# r3eflow-v3.net
KiCad netlist of a schematic drawn in EAGLE
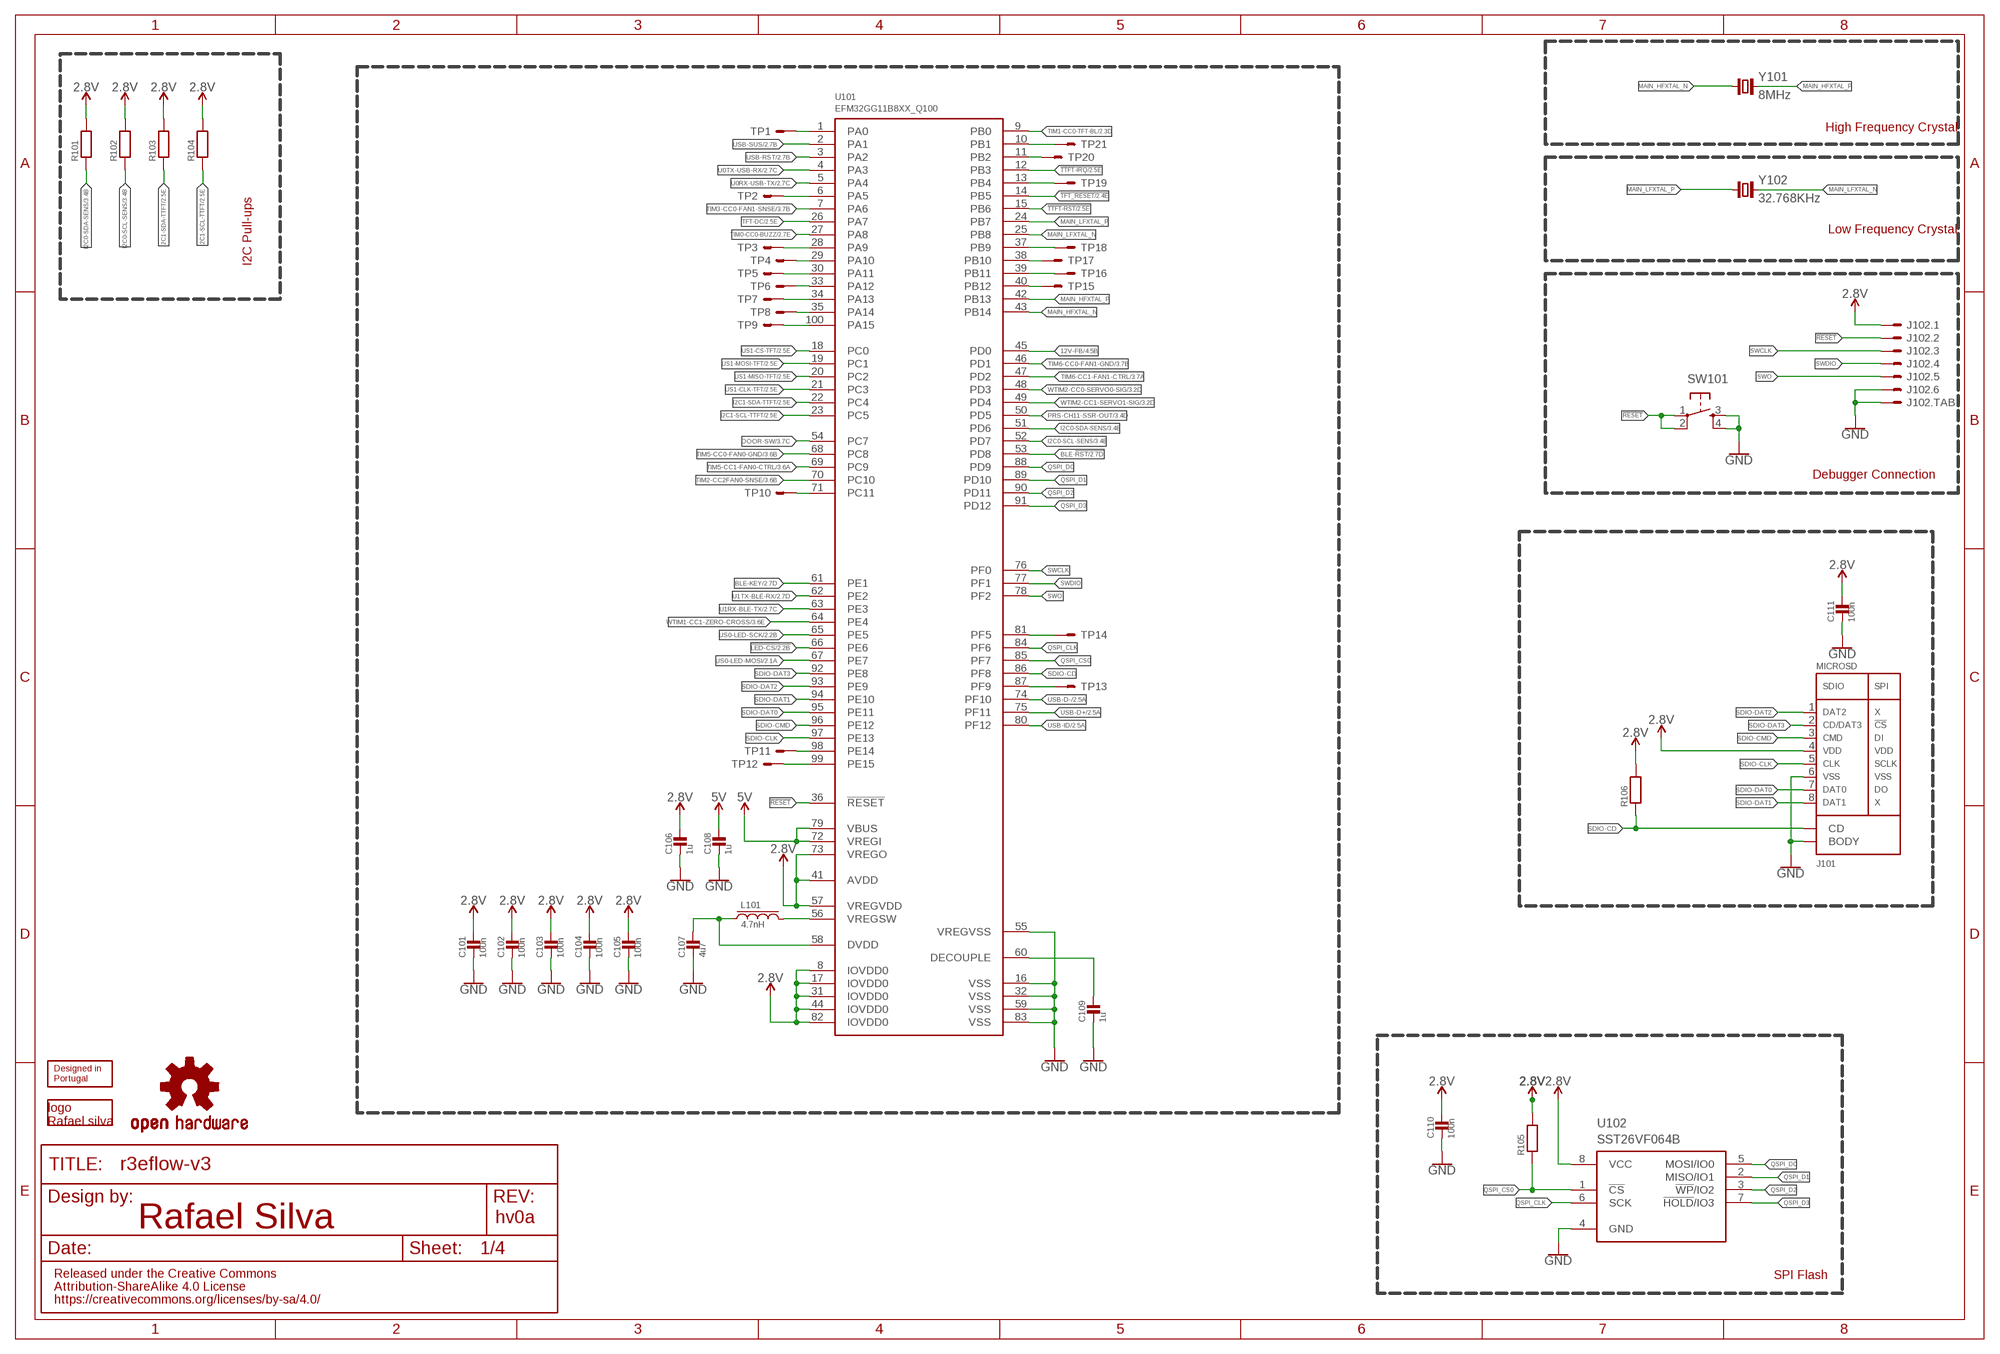
[diagram p0: schematic, sheet 1]
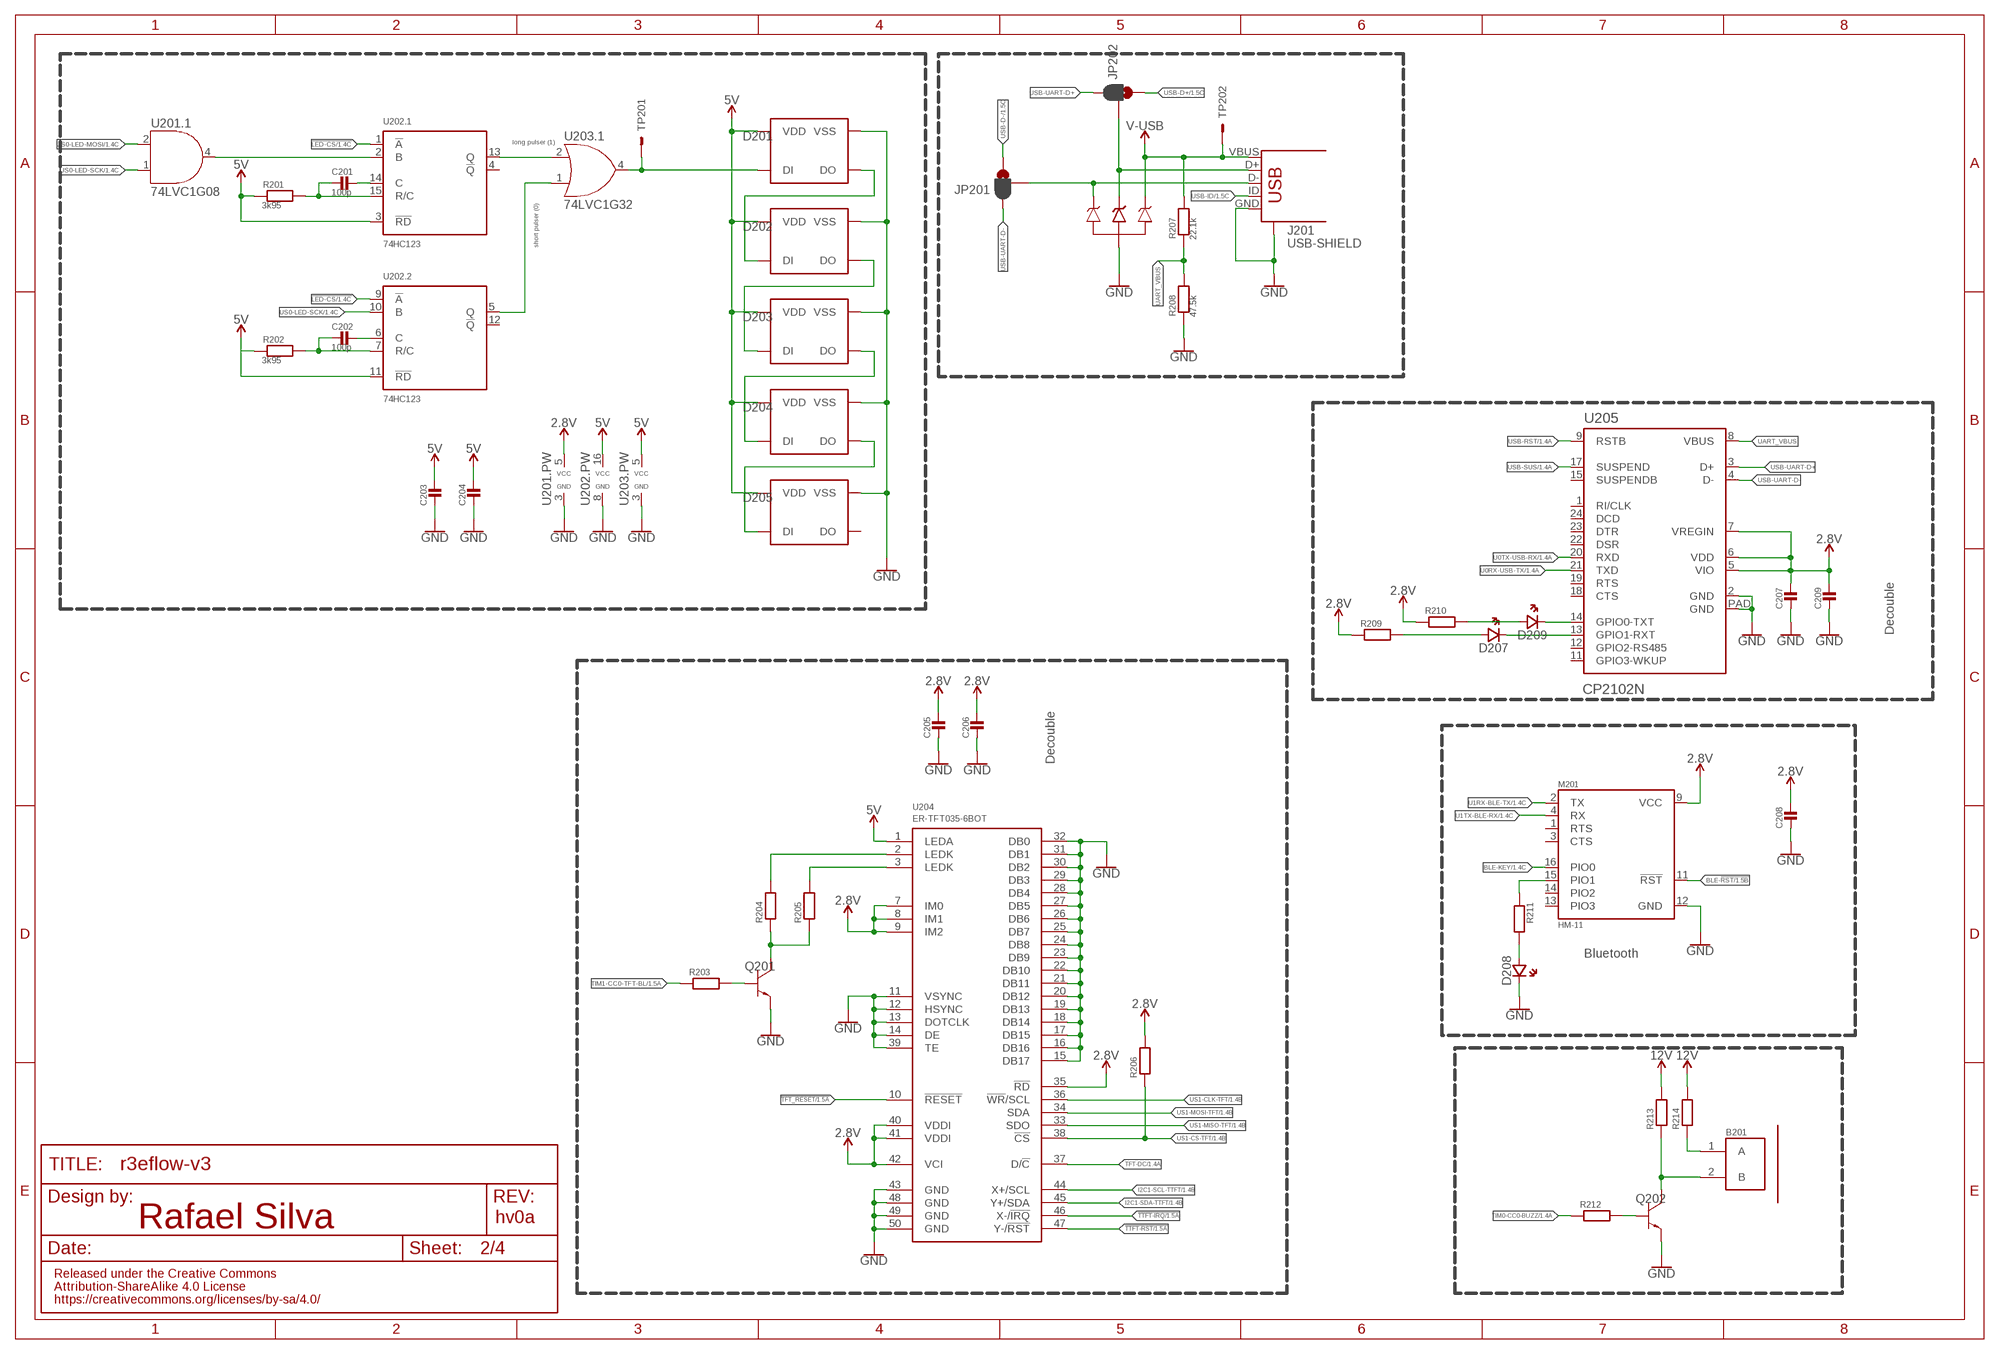
[diagram p1: schematic, sheet 2]
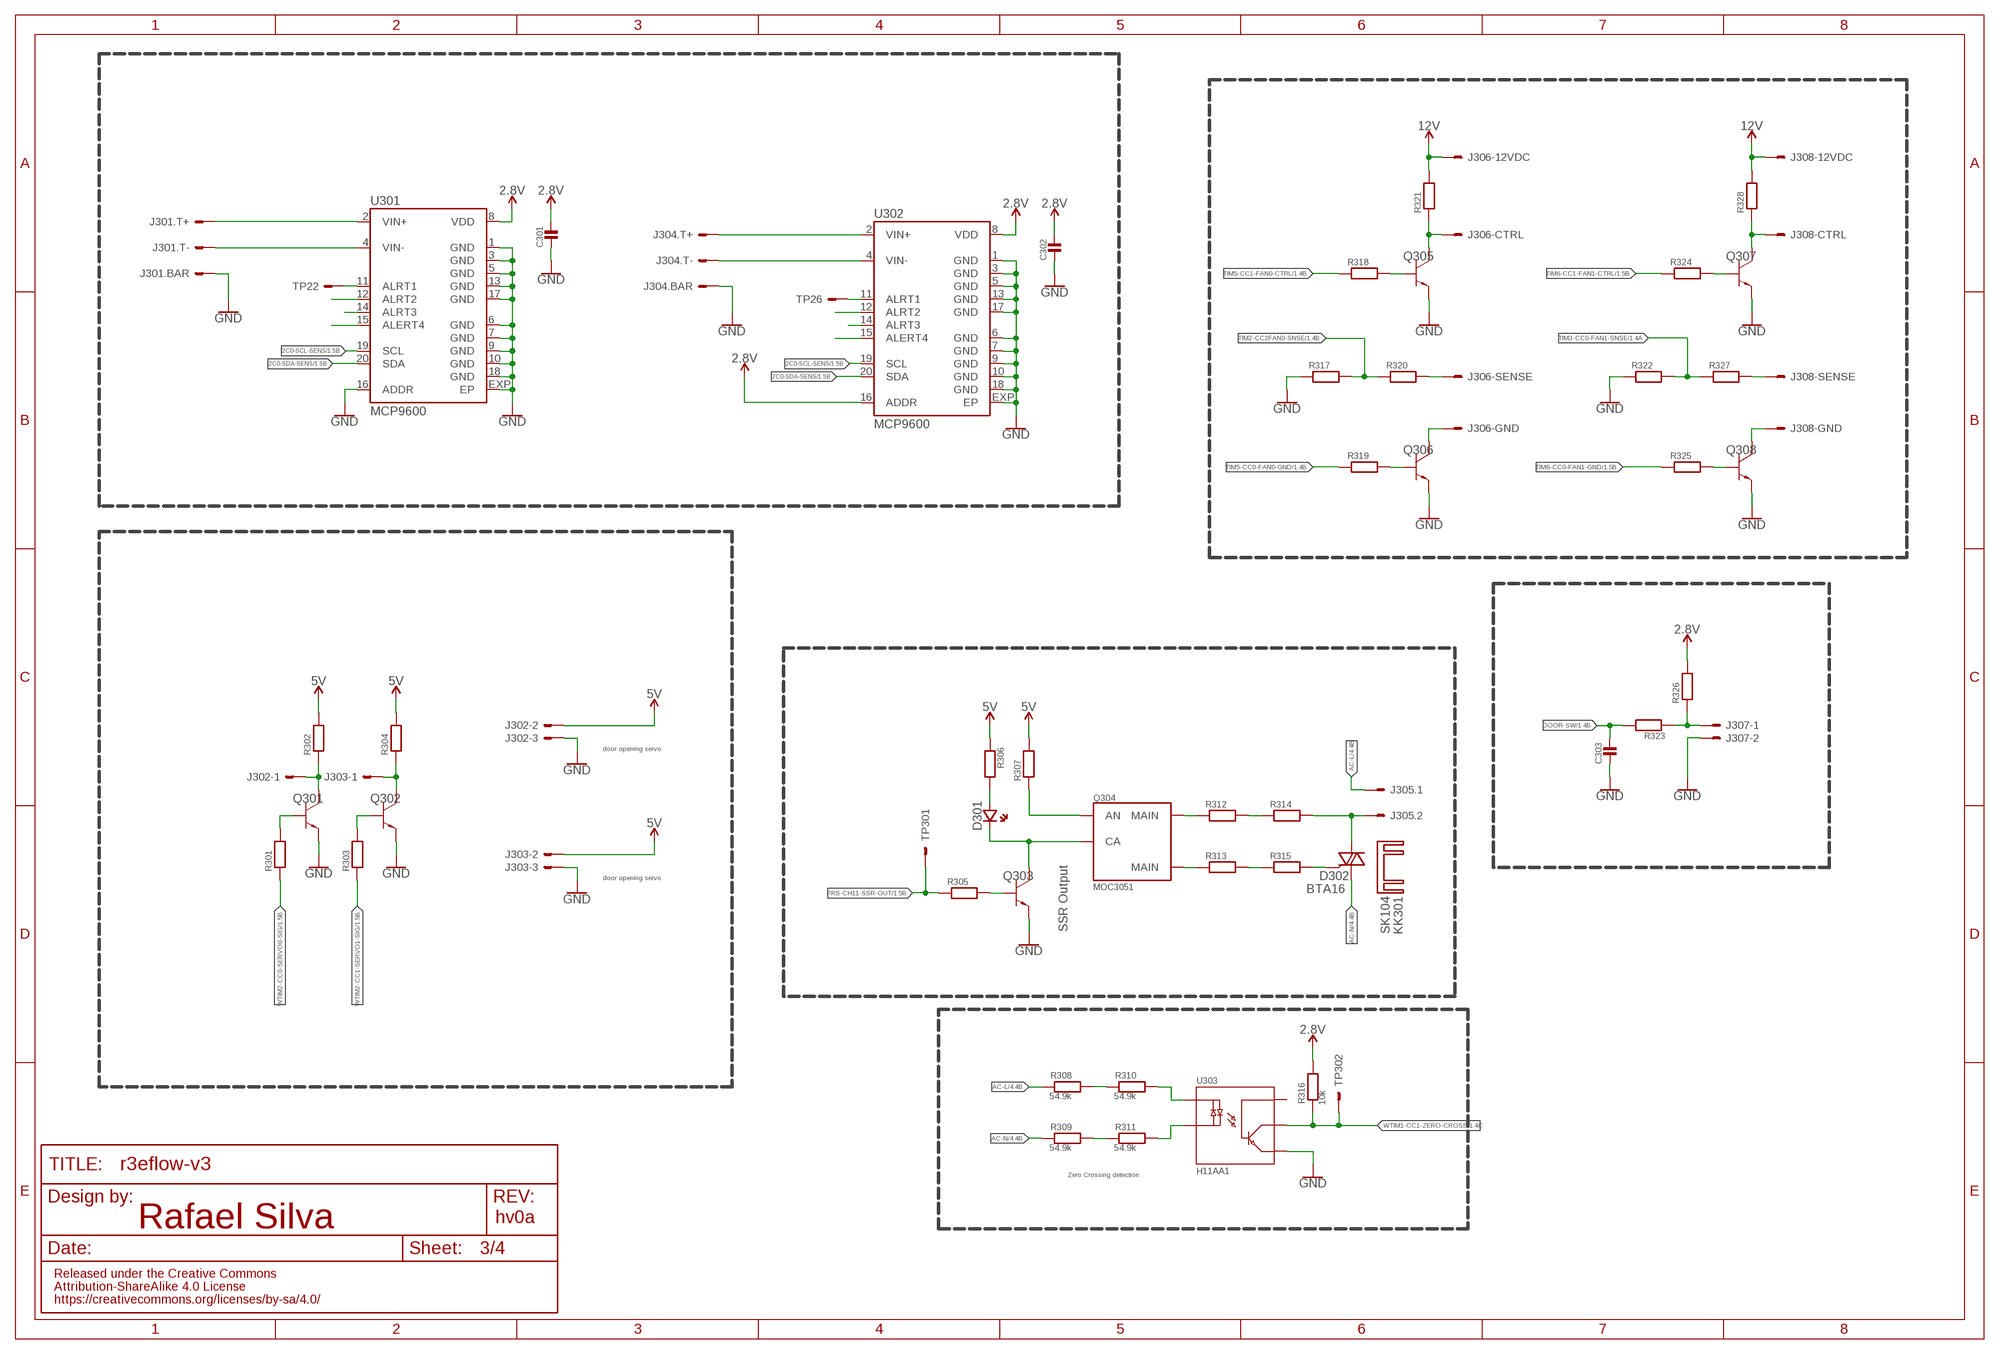
[diagram p2: schematic, sheet 3]
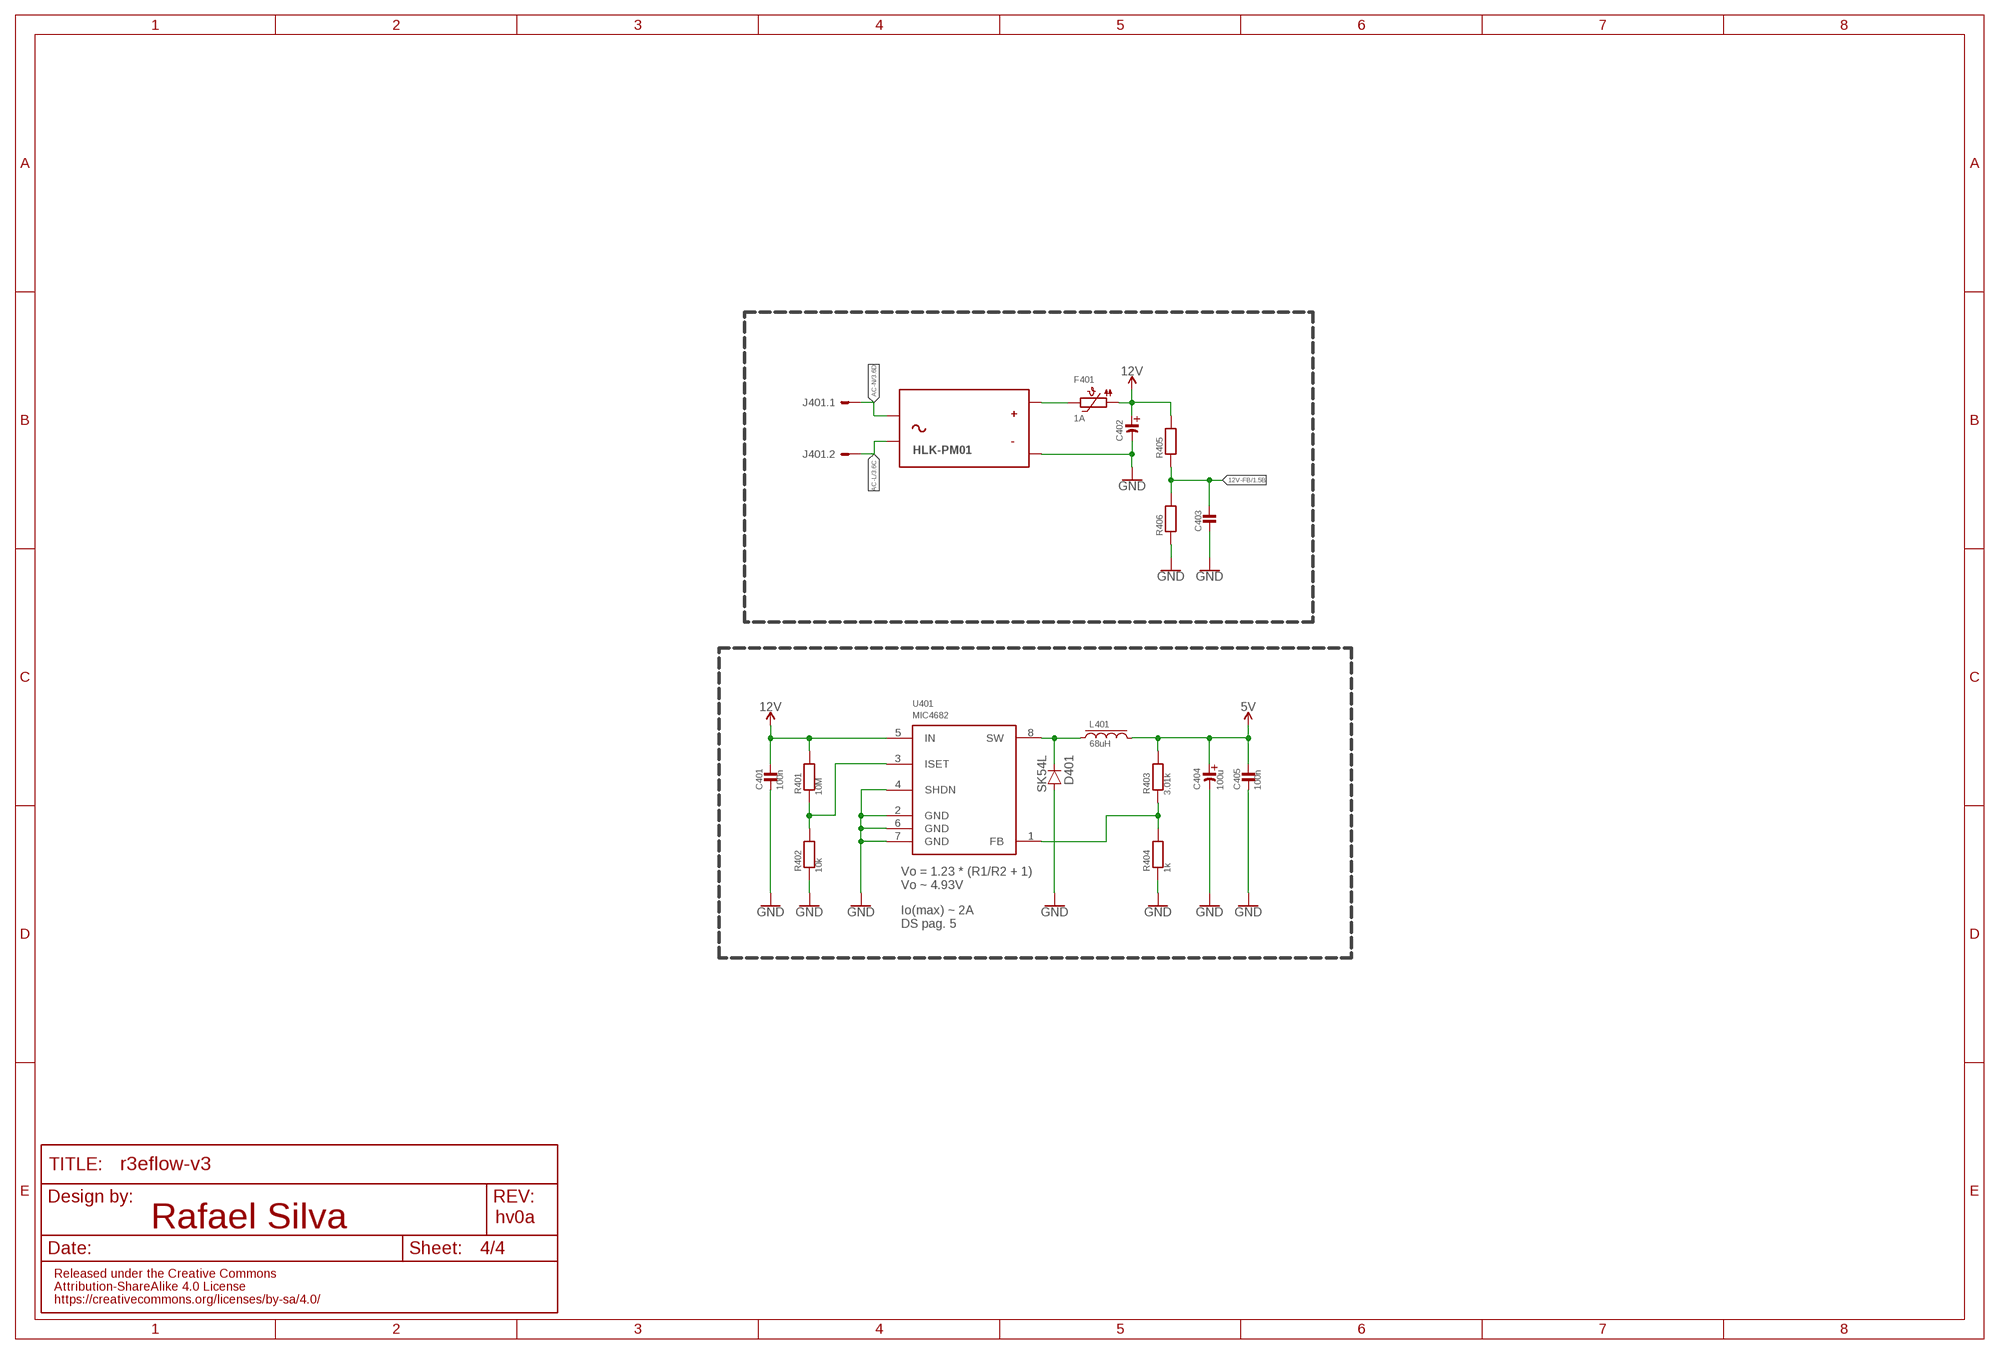
[diagram p3: schematic, sheet 4]

(export (version "E")
  (design (tool "Eeschema 10.0.6"))
  (components
    (comp (ref "B201")
      (value "PKLCS1212E2400-R1")
      (footprint "eagle-import:BUZZ_PIEZO_SMD")
      (libsource (lib "eagle-import") (part "PKLCS1212E2400-R1"))
    )
    (comp (ref "C201")
      (value "100p")
      (footprint "eagle-import:0603_WAVE")
      (libsource (lib "eagle-import") (part "MLCC0603"))
    )
    (comp (ref "C202")
      (value "100p")
      (footprint "eagle-import:0603_WAVE")
      (libsource (lib "eagle-import") (part "MLCC0603"))
    )
    (comp (ref "C203")
      (value "MLCC0603")
      (footprint "eagle-import:0603_WAVE")
      (libsource (lib "eagle-import") (part "MLCC0603"))
    )
    (comp (ref "C204")
      (value "MLCC0603")
      (footprint "eagle-import:0603_WAVE")
      (libsource (lib "eagle-import") (part "MLCC0603"))
    )
    (comp (ref "C205")
      (value "MLCC0603")
      (footprint "eagle-import:0603_WAVE")
      (libsource (lib "eagle-import") (part "MLCC0603"))
    )
    (comp (ref "C206")
      (value "MLCC0603")
      (footprint "eagle-import:0603_WAVE")
      (libsource (lib "eagle-import") (part "MLCC0603"))
    )
    (comp (ref "C207")
      (value "MLCC0603")
      (footprint "eagle-import:0603_WAVE")
      (libsource (lib "eagle-import") (part "MLCC0603"))
    )
    (comp (ref "C208")
      (value "MLCC0603")
      (footprint "eagle-import:0603_WAVE")
      (libsource (lib "eagle-import") (part "MLCC0603"))
    )
    (comp (ref "C209")
      (value "MLCC0603")
      (footprint "eagle-import:0603_WAVE")
      (libsource (lib "eagle-import") (part "MLCC0603"))
    )
    (comp (ref "D201")
      (value "WS2812B")
      (footprint "eagle-import:3535")
      (libsource (lib "eagle-import") (part "WS2812B3535"))
    )
    (comp (ref "D202")
      (value "WS2812B")
      (footprint "eagle-import:3535")
      (libsource (lib "eagle-import") (part "WS2812B3535"))
    )
    (comp (ref "D203")
      (value "WS2812B")
      (footprint "eagle-import:3535")
      (libsource (lib "eagle-import") (part "WS2812B3535"))
    )
    (comp (ref "D204")
      (value "WS2812B")
      (footprint "eagle-import:3535")
      (libsource (lib "eagle-import") (part "WS2812B3535"))
    )
    (comp (ref "D205")
      (value "WS2812B")
      (footprint "eagle-import:3535")
      (libsource (lib "eagle-import") (part "WS2812B3535"))
    )
    (comp (ref "D206")
      (value "SP0503BAHT")
      (footprint "eagle-import:SOT143")
      (libsource (lib "eagle-import") (part "SP0503BAHT"))
    )
    (comp (ref "D207")
      (value "LED0603")
      (footprint "eagle-import:CHIPLED_0603")
      (libsource (lib "eagle-import") (part "LED0603"))
    )
    (comp (ref "D208")
      (value "LED0603")
      (footprint "eagle-import:CHIPLED_0603")
      (libsource (lib "eagle-import") (part "LED0603"))
    )
    (comp (ref "D209")
      (value "LED0603")
      (footprint "eagle-import:CHIPLED_0603")
      (libsource (lib "eagle-import") (part "LED0603"))
    )
    (comp (ref "J201")
      (value "USB-SHIELD")
      (footprint "eagle-import:USB-M-S1")
      (libsource (lib "eagle-import") (part "USB-SHIELD"))
    )
    (comp (ref "JP201")
      (value "JUMPER-SMT_3_1-NC_PASTE_SILK")
      (footprint "eagle-import:SMT-JUMPER_3_1-NC_PASTE_SILK")
      (libsource (lib "eagle-import") (part "JUMPER-SMT_3_1-NC_PASTE_SILK"))
    )
    (comp (ref "JP202")
      (value "JUMPER-SMT_3_1-NC_PASTE_SILK")
      (footprint "eagle-import:SMT-JUMPER_3_1-NC_PASTE_SILK")
      (libsource (lib "eagle-import") (part "JUMPER-SMT_3_1-NC_PASTE_SILK"))
    )
    (comp (ref "M201")
      (value "HM-11")
      (footprint "eagle-import:HM-11")
      (libsource (lib "eagle-import") (part "HM-11"))
    )
    (comp (ref "Q201")
      (value "BC817-40")
      (footprint "eagle-import:SOT-23-3")
      (libsource (lib "eagle-import") (part "BC817-40"))
    )
    (comp (ref "Q202")
      (value "BC817-40")
      (footprint "eagle-import:SOT-23-3")
      (libsource (lib "eagle-import") (part "BC817-40"))
    )
    (comp (ref "R201")
      (value "3k95")
      (footprint "eagle-import:0603_WAVE")
      (libsource (lib "eagle-import") (part "RESISTOR0603"))
    )
    (comp (ref "R202")
      (value "3k95")
      (footprint "eagle-import:0603_WAVE")
      (libsource (lib "eagle-import") (part "RESISTOR0603"))
    )
    (comp (ref "R203")
      (value "RESISTOR0603")
      (footprint "eagle-import:0603_WAVE")
      (libsource (lib "eagle-import") (part "RESISTOR0603"))
    )
    (comp (ref "R204")
      (value "RESISTOR0603")
      (footprint "eagle-import:0603_WAVE")
      (libsource (lib "eagle-import") (part "RESISTOR0603"))
    )
    (comp (ref "R205")
      (value "RESISTOR0603")
      (footprint "eagle-import:0603_WAVE")
      (libsource (lib "eagle-import") (part "RESISTOR0603"))
    )
    (comp (ref "R206")
      (value "RESISTOR0603")
      (footprint "eagle-import:0603_WAVE")
      (libsource (lib "eagle-import") (part "RESISTOR0603"))
    )
    (comp (ref "R207")
      (value "22.1k")
      (footprint "eagle-import:0603_WAVE")
      (libsource (lib "eagle-import") (part "RESISTOR0603"))
    )
    (comp (ref "R208")
      (value "47.5k")
      (footprint "eagle-import:0603_WAVE")
      (libsource (lib "eagle-import") (part "RESISTOR0603"))
    )
    (comp (ref "R209")
      (value "RESISTOR0603")
      (footprint "eagle-import:0603_WAVE")
      (libsource (lib "eagle-import") (part "RESISTOR0603"))
    )
    (comp (ref "R210")
      (value "RESISTOR0603")
      (footprint "eagle-import:0603_WAVE")
      (libsource (lib "eagle-import") (part "RESISTOR0603"))
    )
    (comp (ref "R211")
      (value "RESISTOR0603")
      (footprint "eagle-import:0603_WAVE")
      (libsource (lib "eagle-import") (part "RESISTOR0603"))
    )
    (comp (ref "R212")
      (value "RESISTOR0603")
      (footprint "eagle-import:0603_WAVE")
      (libsource (lib "eagle-import") (part "RESISTOR0603"))
    )
    (comp (ref "R213")
      (value "RESISTOR0603")
      (footprint "eagle-import:0603_WAVE")
      (libsource (lib "eagle-import") (part "RESISTOR0603"))
    )
    (comp (ref "R214")
      (value "RESISTOR0603")
      (footprint "eagle-import:0603_WAVE")
      (libsource (lib "eagle-import") (part "RESISTOR0603"))
    )
    (comp (ref "TP201")
      (value "TEST_POINT")
      (footprint "eagle-import:TEST_POINT")
      (libsource (lib "eagle-import") (part "TEST_POINT"))
    )
    (comp (ref "TP202")
      (value "TEST_POINT")
      (footprint "eagle-import:TEST_POINT")
      (libsource (lib "eagle-import") (part "TEST_POINT"))
    )
    (comp (ref "U201")
      (value "74LVC1G08")
      (footprint "eagle-import:SC-70-5")
      (libsource (lib "eagle-import") (part "74LVC1G08"))
    )
    (comp (ref "U202")
      (value "74HC123")
      (footprint "eagle-import:TSSOP-16")
      (libsource (lib "eagle-import") (part "74HC123"))
    )
    (comp (ref "U203")
      (value "74LVC1G32")
      (footprint "eagle-import:SC-70-5")
      (libsource (lib "eagle-import") (part "74LVC1G32"))
    )
    (comp (ref "U204")
      (value "ER-TFT035-6BOT")
      (footprint "eagle-import:ZIF50-TFT_BACK")
      (libsource (lib "eagle-import") (part "ER-TFT035-6BOT"))
    )
    (comp (ref "U205")
      (value "CP2102N")
      (footprint "eagle-import:QFN24")
      (libsource (lib "eagle-import") (part "CP2102N"))
    )
    (comp (ref "C301")
      (value "MLCC0603")
      (footprint "eagle-import:0603_WAVE")
      (libsource (lib "eagle-import") (part "MLCC0603"))
    )
    (comp (ref "C302")
      (value "MLCC0603")
      (footprint "eagle-import:0603_WAVE")
      (libsource (lib "eagle-import") (part "MLCC0603"))
    )
    (comp (ref "C303")
      (value "MLCC0603")
      (footprint "eagle-import:0603_WAVE")
      (libsource (lib "eagle-import") (part "MLCC0603"))
    )
    (comp (ref "D301")
      (value "LED0603")
      (footprint "eagle-import:CHIPLED_0603")
      (libsource (lib "eagle-import") (part "LED0603"))
    )
    (comp (ref "D302")
      (value "BTA16")
      (footprint "eagle-import:TO220DS")
      (libsource (lib "eagle-import") (part "BTA16"))
    )
    (comp (ref "J301")
      (value "PCC-SMP")
      (footprint "eagle-import:PCC-SMP")
      (libsource (lib "eagle-import") (part "PCC-SMP"))
    )
    (comp (ref "J302")
      (value "3X1_2.54")
      (footprint "eagle-import:3X1_2.54")
      (libsource (lib "eagle-import") (part "3X1_2.54"))
    )
    (comp (ref "J303")
      (value "3X1_2.54")
      (footprint "eagle-import:3X1_2.54")
      (libsource (lib "eagle-import") (part "3X1_2.54"))
    )
    (comp (ref "J304")
      (value "PCC-SMP")
      (footprint "eagle-import:PCC-SMP")
      (libsource (lib "eagle-import") (part "PCC-SMP"))
    )
    (comp (ref "J305")
      (value "2EDG-2P")
      (footprint "eagle-import:2EDG-2P")
      (libsource (lib "eagle-import") (part "2EDG-2P"))
    )
    (comp (ref "J306")
      (value "4P-PC-FAN")
      (footprint "eagle-import:KF2510-3+1P")
      (libsource (lib "eagle-import") (part "4P-PC-FAN"))
    )
    (comp (ref "J307")
      (value "2X1_2.54")
      (footprint "eagle-import:2X1_2.54")
      (libsource (lib "eagle-import") (part "2X1_2.54"))
    )
    (comp (ref "J308")
      (value "4P-PC-FAN")
      (footprint "eagle-import:KF2510-3+1P")
      (libsource (lib "eagle-import") (part "4P-PC-FAN"))
    )
    (comp (ref "KK301")
      (value "SK104")
      (footprint "eagle-import:SK104")
      (libsource (lib "eagle-import") (part "SK104"))
    )
    (comp (ref "Q301")
      (value "BC817-40")
      (footprint "eagle-import:SOT-23-3")
      (libsource (lib "eagle-import") (part "BC817-40"))
    )
    (comp (ref "Q302")
      (value "BC817-40")
      (footprint "eagle-import:SOT-23-3")
      (libsource (lib "eagle-import") (part "BC817-40"))
    )
    (comp (ref "Q303")
      (value "BC817-40")
      (footprint "eagle-import:SOT-23-3")
      (libsource (lib "eagle-import") (part "BC817-40"))
    )
    (comp (ref "Q304")
      (value "MOC3051")
      (footprint "eagle-import:DIP-6-SMD")
      (libsource (lib "eagle-import") (part "MOC3051"))
    )
    (comp (ref "Q305")
      (value "BC817-40")
      (footprint "eagle-import:SOT-23-3")
      (libsource (lib "eagle-import") (part "BC817-40"))
    )
    (comp (ref "Q306")
      (value "BC817-40")
      (footprint "eagle-import:SOT-23-3")
      (libsource (lib "eagle-import") (part "BC817-40"))
    )
    (comp (ref "Q307")
      (value "BC817-40")
      (footprint "eagle-import:SOT-23-3")
      (libsource (lib "eagle-import") (part "BC817-40"))
    )
    (comp (ref "Q308")
      (value "BC817-40")
      (footprint "eagle-import:SOT-23-3")
      (libsource (lib "eagle-import") (part "BC817-40"))
    )
    (comp (ref "R301")
      (value "RESISTOR0603")
      (footprint "eagle-import:0603_WAVE")
      (libsource (lib "eagle-import") (part "RESISTOR0603"))
    )
    (comp (ref "R302")
      (value "RESISTOR0603")
      (footprint "eagle-import:0603_WAVE")
      (libsource (lib "eagle-import") (part "RESISTOR0603"))
    )
    (comp (ref "R303")
      (value "RESISTOR0603")
      (footprint "eagle-import:0603_WAVE")
      (libsource (lib "eagle-import") (part "RESISTOR0603"))
    )
    (comp (ref "R304")
      (value "RESISTOR0603")
      (footprint "eagle-import:0603_WAVE")
      (libsource (lib "eagle-import") (part "RESISTOR0603"))
    )
    (comp (ref "R305")
      (value "RESISTOR0603")
      (footprint "eagle-import:0603_WAVE")
      (libsource (lib "eagle-import") (part "RESISTOR0603"))
    )
    (comp (ref "R306")
      (value "RESISTOR0603")
      (footprint "eagle-import:0603_WAVE")
      (libsource (lib "eagle-import") (part "RESISTOR0603"))
    )
    (comp (ref "R307")
      (value "RESISTOR0603")
      (footprint "eagle-import:0603_WAVE")
      (libsource (lib "eagle-import") (part "RESISTOR0603"))
    )
    (comp (ref "R308")
      (value "54.9k")
      (footprint "eagle-import:_1206")
      (libsource (lib "eagle-import") (part "RESISTOR_1206"))
    )
    (comp (ref "R309")
      (value "54.9k")
      (footprint "eagle-import:_1206")
      (libsource (lib "eagle-import") (part "RESISTOR_1206"))
    )
    (comp (ref "R310")
      (value "54.9k")
      (footprint "eagle-import:_1206")
      (libsource (lib "eagle-import") (part "RESISTOR_1206"))
    )
    (comp (ref "R311")
      (value "54.9k")
      (footprint "eagle-import:_1206")
      (libsource (lib "eagle-import") (part "RESISTOR_1206"))
    )
    (comp (ref "R312")
      (value "RESISTOR_1206")
      (footprint "eagle-import:_1206")
      (libsource (lib "eagle-import") (part "RESISTOR_1206"))
    )
    (comp (ref "R313")
      (value "RESISTOR_1206")
      (footprint "eagle-import:_1206")
      (libsource (lib "eagle-import") (part "RESISTOR_1206"))
    )
    (comp (ref "R314")
      (value "RESISTOR_1206")
      (footprint "eagle-import:_1206")
      (libsource (lib "eagle-import") (part "RESISTOR_1206"))
    )
    (comp (ref "R315")
      (value "RESISTOR_1206")
      (footprint "eagle-import:_1206")
      (libsource (lib "eagle-import") (part "RESISTOR_1206"))
    )
    (comp (ref "R316")
      (value "10k")
      (footprint "eagle-import:0603_WAVE")
      (libsource (lib "eagle-import") (part "RESISTOR0603"))
    )
    (comp (ref "R317")
      (value "RESISTOR0603")
      (footprint "eagle-import:0603_WAVE")
      (libsource (lib "eagle-import") (part "RESISTOR0603"))
    )
    (comp (ref "R318")
      (value "RESISTOR0603")
      (footprint "eagle-import:0603_WAVE")
      (libsource (lib "eagle-import") (part "RESISTOR0603"))
    )
    (comp (ref "R319")
      (value "RESISTOR0603")
      (footprint "eagle-import:0603_WAVE")
      (libsource (lib "eagle-import") (part "RESISTOR0603"))
    )
    (comp (ref "R320")
      (value "RESISTOR0603")
      (footprint "eagle-import:0603_WAVE")
      (libsource (lib "eagle-import") (part "RESISTOR0603"))
    )
    (comp (ref "R321")
      (value "RESISTOR0603")
      (footprint "eagle-import:0603_WAVE")
      (libsource (lib "eagle-import") (part "RESISTOR0603"))
    )
    (comp (ref "R322")
      (value "RESISTOR0603")
      (footprint "eagle-import:0603_WAVE")
      (libsource (lib "eagle-import") (part "RESISTOR0603"))
    )
    (comp (ref "R323")
      (value "RESISTOR0603")
      (footprint "eagle-import:0603_WAVE")
      (libsource (lib "eagle-import") (part "RESISTOR0603"))
    )
    (comp (ref "R324")
      (value "RESISTOR0603")
      (footprint "eagle-import:0603_WAVE")
      (libsource (lib "eagle-import") (part "RESISTOR0603"))
    )
    (comp (ref "R325")
      (value "RESISTOR0603")
      (footprint "eagle-import:0603_WAVE")
      (libsource (lib "eagle-import") (part "RESISTOR0603"))
    )
    (comp (ref "R326")
      (value "RESISTOR0603")
      (footprint "eagle-import:0603_WAVE")
      (libsource (lib "eagle-import") (part "RESISTOR0603"))
    )
    (comp (ref "R327")
      (value "RESISTOR0603")
      (footprint "eagle-import:0603_WAVE")
      (libsource (lib "eagle-import") (part "RESISTOR0603"))
    )
    (comp (ref "R328")
      (value "RESISTOR0603")
      (footprint "eagle-import:0603_WAVE")
      (libsource (lib "eagle-import") (part "RESISTOR0603"))
    )
    (comp (ref "TP22")
      (value "TEST_POINT")
      (footprint "eagle-import:TEST_POINT")
      (libsource (lib "eagle-import") (part "TEST_POINT"))
    )
    (comp (ref "TP26")
      (value "TEST_POINT")
      (footprint "eagle-import:TEST_POINT")
      (libsource (lib "eagle-import") (part "TEST_POINT"))
    )
    (comp (ref "TP301")
      (value "TEST_POINT")
      (footprint "eagle-import:TEST_POINT")
      (libsource (lib "eagle-import") (part "TEST_POINT"))
    )
    (comp (ref "TP302")
      (value "TEST_POINT")
      (footprint "eagle-import:TEST_POINT")
      (libsource (lib "eagle-import") (part "TEST_POINT"))
    )
    (comp (ref "U301")
      (value "MCP9600")
      (footprint "eagle-import:TQFN20-5X5")
      (libsource (lib "eagle-import") (part "MCP9600"))
    )
    (comp (ref "U302")
      (value "MCP9600")
      (footprint "eagle-import:TQFN20-5X5")
      (libsource (lib "eagle-import") (part "MCP9600"))
    )
    (comp (ref "U303")
      (value "H11AA1")
      (footprint "eagle-import:DIP-6-SMD")
      (libsource (lib "eagle-import") (part "H11AA1"))
    )
    (comp (ref "ACDC401")
      (value "HLK-PM01")
      (footprint "eagle-import:HLK-PM01")
      (libsource (lib "eagle-import") (part "HLK-PM01"))
    )
    (comp (ref "C401")
      (value "100n")
      (footprint "eagle-import:0603_WAVE")
      (libsource (lib "eagle-import") (part "MLCC0603"))
    )
    (comp (ref "C402")
      (value "CAPACITOR_ELD")
      (footprint "eagle-import:PANASONIC_D")
      (libsource (lib "eagle-import") (part "CAPACITOR_ELD"))
    )
    (comp (ref "C403")
      (value "MLCC0603")
      (footprint "eagle-import:0603_WAVE")
      (libsource (lib "eagle-import") (part "MLCC0603"))
    )
    (comp (ref "C404")
      (value "100u")
      (footprint "eagle-import:PANASONIC_D")
      (libsource (lib "eagle-import") (part "CAPACITOR_ELD"))
    )
    (comp (ref "C405")
      (value "100n")
      (footprint "eagle-import:0603_WAVE")
      (libsource (lib "eagle-import") (part "MLCC0603"))
    )
    (comp (ref "D401")
      (value "SK54L")
      (footprint "eagle-import:DO214AA")
      (libsource (lib "eagle-import") (part "SK54L"))
    )
    (comp (ref "F401")
      (value "1A")
      (footprint "eagle-import:PTC1812")
      (libsource (lib "eagle-import") (part "PTC1812"))
    )
    (comp (ref "J401")
      (value "2EDG-2P")
      (footprint "eagle-import:2EDG-2P")
      (libsource (lib "eagle-import") (part "2EDG-2P"))
    )
    (comp (ref "L401")
      (value "68uH")
      (footprint "eagle-import:1207")
      (libsource (lib "eagle-import") (part "INDUCTOR1207"))
    )
    (comp (ref "R401")
      (value "10M")
      (footprint "eagle-import:0603_WAVE")
      (libsource (lib "eagle-import") (part "RESISTOR0603"))
    )
    (comp (ref "R402")
      (value "10k")
      (footprint "eagle-import:0603_WAVE")
      (libsource (lib "eagle-import") (part "RESISTOR0603"))
    )
    (comp (ref "R403")
      (value "3.01k")
      (footprint "eagle-import:0603_WAVE")
      (libsource (lib "eagle-import") (part "RESISTOR0603"))
    )
    (comp (ref "R404")
      (value "1k")
      (footprint "eagle-import:0603_WAVE")
      (libsource (lib "eagle-import") (part "RESISTOR0603"))
    )
    (comp (ref "R405")
      (value "RESISTOR0603")
      (footprint "eagle-import:0603_WAVE")
      (libsource (lib "eagle-import") (part "RESISTOR0603"))
    )
    (comp (ref "R406")
      (value "RESISTOR0603")
      (footprint "eagle-import:0603_WAVE")
      (libsource (lib "eagle-import") (part "RESISTOR0603"))
    )
    (comp (ref "U401")
      (value "MIC4682")
      (footprint "eagle-import:SOIC8")
      (libsource (lib "eagle-import") (part "MIC4682"))
    )
    (comp (ref "C101")
      (value "100n")
      (footprint "eagle-import:0603_WAVE")
      (libsource (lib "eagle-import") (part "MLCC0603"))
    )
    (comp (ref "C102")
      (value "100n")
      (footprint "eagle-import:0603_WAVE")
      (libsource (lib "eagle-import") (part "MLCC0603"))
    )
    (comp (ref "C103")
      (value "100n")
      (footprint "eagle-import:0603_WAVE")
      (libsource (lib "eagle-import") (part "MLCC0603"))
    )
    (comp (ref "C104")
      (value "100n")
      (footprint "eagle-import:0603_WAVE")
      (libsource (lib "eagle-import") (part "MLCC0603"))
    )
    (comp (ref "C105")
      (value "100n")
      (footprint "eagle-import:0603_WAVE")
      (libsource (lib "eagle-import") (part "MLCC0603"))
    )
    (comp (ref "C106")
      (value "1u")
      (footprint "eagle-import:0603_WAVE")
      (libsource (lib "eagle-import") (part "MLCC0603"))
    )
    (comp (ref "C107")
      (value "4u7")
      (footprint "eagle-import:0603_WAVE")
      (libsource (lib "eagle-import") (part "MLCC0603"))
    )
    (comp (ref "C108")
      (value "1u")
      (footprint "eagle-import:0603_WAVE")
      (libsource (lib "eagle-import") (part "MLCC0603"))
    )
    (comp (ref "C109")
      (value "1u")
      (footprint "eagle-import:0603_WAVE")
      (libsource (lib "eagle-import") (part "MLCC0603"))
    )
    (comp (ref "C110")
      (value "100n")
      (footprint "eagle-import:0603_WAVE")
      (libsource (lib "eagle-import") (part "MLCC0603"))
    )
    (comp (ref "C111")
      (value "100n")
      (footprint "eagle-import:0603_WAVE")
      (libsource (lib "eagle-import") (part "MLCC0603"))
    )
    (comp (ref "J101")
      (value "MICROSD")
      (footprint "eagle-import:MICRO-SD")
      (libsource (lib "eagle-import") (part "MICROSD"))
    )
    (comp (ref "J102")
      (value "SH-6")
      (footprint "eagle-import:SM06B-SSR-H-TB")
      (libsource (lib "eagle-import") (part "SH-6"))
    )
    (comp (ref "L101")
      (value "4.7nH")
      (footprint "eagle-import:_0805")
      (libsource (lib "eagle-import") (part "INDUCTOR"))
    )
    (comp (ref "LOGO101")
      (value "DESIGNEDINPT")
      (footprint "eagle-import:DESIGNEDINPT")
      (libsource (lib "eagle-import") (part "DESIGNEDINPT"))
    )
    (comp (ref "LOGO102")
      (value "RAFAEL_SILVA")
      (footprint "eagle-import:RAFAEL_SILVA_5MM_ALT_3")
      (libsource (lib "eagle-import") (part "RAFAEL_SILVA"))
    )
    (comp (ref "LOGO103")
      (value "OSHW-LOGOL")
      (footprint "eagle-import:OSHW-LOGO-L")
      (libsource (lib "eagle-import") (part "OSHW-LOGOL"))
    )
    (comp (ref "R101")
      (value "RESISTOR0603")
      (footprint "eagle-import:0603_WAVE")
      (libsource (lib "eagle-import") (part "RESISTOR0603"))
    )
    (comp (ref "R102")
      (value "RESISTOR0603")
      (footprint "eagle-import:0603_WAVE")
      (libsource (lib "eagle-import") (part "RESISTOR0603"))
    )
    (comp (ref "R103")
      (value "RESISTOR0603")
      (footprint "eagle-import:0603_WAVE")
      (libsource (lib "eagle-import") (part "RESISTOR0603"))
    )
    (comp (ref "R104")
      (value "RESISTOR0603")
      (footprint "eagle-import:0603_WAVE")
      (libsource (lib "eagle-import") (part "RESISTOR0603"))
    )
    (comp (ref "R105")
      (value "RESISTOR0603")
      (footprint "eagle-import:0603_WAVE")
      (libsource (lib "eagle-import") (part "RESISTOR0603"))
    )
    (comp (ref "R106")
      (value "RESISTOR0603")
      (footprint "eagle-import:0603_WAVE")
      (libsource (lib "eagle-import") (part "RESISTOR0603"))
    )
    (comp (ref "SW101")
      (value "PUSH_BUTTON")
      (footprint "eagle-import:PUSH_BUTTON")
      (libsource (lib "eagle-import") (part "PUSH_BUTTON"))
    )
    (comp (ref "TP1")
      (value "TEST_POINT")
      (footprint "eagle-import:TEST_POINT")
      (libsource (lib "eagle-import") (part "TEST_POINT"))
    )
    (comp (ref "TP2")
      (value "TEST_POINT")
      (footprint "eagle-import:TEST_POINT")
      (libsource (lib "eagle-import") (part "TEST_POINT"))
    )
    (comp (ref "TP3")
      (value "TEST_POINT")
      (footprint "eagle-import:TEST_POINT")
      (libsource (lib "eagle-import") (part "TEST_POINT"))
    )
    (comp (ref "TP4")
      (value "TEST_POINT")
      (footprint "eagle-import:TEST_POINT")
      (libsource (lib "eagle-import") (part "TEST_POINT"))
    )
    (comp (ref "TP5")
      (value "TEST_POINT")
      (footprint "eagle-import:TEST_POINT")
      (libsource (lib "eagle-import") (part "TEST_POINT"))
    )
    (comp (ref "TP6")
      (value "TEST_POINT")
      (footprint "eagle-import:TEST_POINT")
      (libsource (lib "eagle-import") (part "TEST_POINT"))
    )
    (comp (ref "TP7")
      (value "TEST_POINT")
      (footprint "eagle-import:TEST_POINT")
      (libsource (lib "eagle-import") (part "TEST_POINT"))
    )
    (comp (ref "TP8")
      (value "TEST_POINT")
      (footprint "eagle-import:TEST_POINT")
      (libsource (lib "eagle-import") (part "TEST_POINT"))
    )
    (comp (ref "TP9")
      (value "TEST_POINT")
      (footprint "eagle-import:TEST_POINT")
      (libsource (lib "eagle-import") (part "TEST_POINT"))
    )
    (comp (ref "TP10")
      (value "TEST_POINT")
      (footprint "eagle-import:TEST_POINT")
      (libsource (lib "eagle-import") (part "TEST_POINT"))
    )
    (comp (ref "TP11")
      (value "TEST_POINT")
      (footprint "eagle-import:TEST_POINT")
      (libsource (lib "eagle-import") (part "TEST_POINT"))
    )
    (comp (ref "TP12")
      (value "TEST_POINT")
      (footprint "eagle-import:TEST_POINT")
      (libsource (lib "eagle-import") (part "TEST_POINT"))
    )
    (comp (ref "TP13")
      (value "TEST_POINT")
      (footprint "eagle-import:TEST_POINT")
      (libsource (lib "eagle-import") (part "TEST_POINT"))
    )
    (comp (ref "TP14")
      (value "TEST_POINT")
      (footprint "eagle-import:TEST_POINT")
      (libsource (lib "eagle-import") (part "TEST_POINT"))
    )
    (comp (ref "TP15")
      (value "TEST_POINT")
      (footprint "eagle-import:TEST_POINT")
      (libsource (lib "eagle-import") (part "TEST_POINT"))
    )
    (comp (ref "TP16")
      (value "TEST_POINT")
      (footprint "eagle-import:TEST_POINT")
      (libsource (lib "eagle-import") (part "TEST_POINT"))
    )
    (comp (ref "TP17")
      (value "TEST_POINT")
      (footprint "eagle-import:TEST_POINT")
      (libsource (lib "eagle-import") (part "TEST_POINT"))
    )
    (comp (ref "TP18")
      (value "TEST_POINT")
      (footprint "eagle-import:TEST_POINT")
      (libsource (lib "eagle-import") (part "TEST_POINT"))
    )
    (comp (ref "TP19")
      (value "TEST_POINT")
      (footprint "eagle-import:TEST_POINT")
      (libsource (lib "eagle-import") (part "TEST_POINT"))
    )
    (comp (ref "TP20")
      (value "TEST_POINT")
      (footprint "eagle-import:TEST_POINT")
      (libsource (lib "eagle-import") (part "TEST_POINT"))
    )
    (comp (ref "TP21")
      (value "TEST_POINT")
      (footprint "eagle-import:TEST_POINT")
      (libsource (lib "eagle-import") (part "TEST_POINT"))
    )
    (comp (ref "U101")
      (value "EFM32GG11B8XX_Q100")
      (footprint "eagle-import:QFP100")
      (libsource (lib "eagle-import") (part "EFM32GG11B8XX_Q100"))
    )
    (comp (ref "U102")
      (value "SST26VF064B")
      (footprint "eagle-import:WSOIC8")
      (libsource (lib "eagle-import") (part "SST26VF064B"))
    )
    (comp (ref "Y101")
      (value "8MHz")
      (footprint "eagle-import:2-SMD-5X3")
      (libsource (lib "eagle-import") (part "CRYSTALNX5032GA"))
    )
    (comp (ref "Y102")
      (value "32.768KHz")
      (footprint "eagle-import:CM200S")
      (libsource (lib "eagle-import") (part "CRYSTALCM200S"))
    )
  )
  (nets
    (net (code "1") (name "2.8V") (class "Default")
      (node (ref "C101") (pin "P$1") (pinfunction "P$1_P$1") (pintype "bidirectional"))
      (node (ref "C102") (pin "P$1") (pinfunction "P$1_P$1") (pintype "bidirectional"))
      (node (ref "C103") (pin "P$1") (pinfunction "P$1_P$1") (pintype "bidirectional"))
      (node (ref "C104") (pin "P$1") (pinfunction "P$1_P$1") (pintype "bidirectional"))
      (node (ref "C105") (pin "P$1") (pinfunction "P$1_P$1") (pintype "bidirectional"))
      (node (ref "C106") (pin "P$1") (pinfunction "P$1_P$1") (pintype "bidirectional"))
      (node (ref "C110") (pin "P$1") (pinfunction "P$1_P$1") (pintype "bidirectional"))
      (node (ref "C111") (pin "P$1") (pinfunction "P$1_P$1") (pintype "bidirectional"))
      (node (ref "C205") (pin "P$1") (pinfunction "P$1_P$1") (pintype "bidirectional"))
      (node (ref "C206") (pin "P$1") (pinfunction "P$1_P$1") (pintype "bidirectional"))
      (node (ref "C207") (pin "P$1") (pinfunction "P$1_P$1") (pintype "bidirectional"))
      (node (ref "C208") (pin "P$1") (pinfunction "P$1_P$1") (pintype "bidirectional"))
      (node (ref "C209") (pin "P$1") (pinfunction "P$1_P$1") (pintype "bidirectional"))
      (node (ref "C301") (pin "P$1") (pinfunction "P$1_P$1") (pintype "bidirectional"))
      (node (ref "C302") (pin "P$1") (pinfunction "P$1_P$1") (pintype "bidirectional"))
      (node (ref "J101") (pin "4") (pinfunction "4_4") (pintype "bidirectional"))
      (node (ref "J102") (pin "1") (pinfunction "S_1") (pintype "passive"))
      (node (ref "M201") (pin "9") (pinfunction "VCC_9") (pintype "bidirectional"))
      (node (ref "R101") (pin "P$2") (pinfunction "P$2_P$2") (pintype "bidirectional"))
      (node (ref "R102") (pin "P$2") (pinfunction "P$2_P$2") (pintype "bidirectional"))
      (node (ref "R103") (pin "P$2") (pinfunction "P$2_P$2") (pintype "bidirectional"))
      (node (ref "R104") (pin "P$2") (pinfunction "P$2_P$2") (pintype "bidirectional"))
      (node (ref "R105") (pin "P$2") (pinfunction "P$2_P$2") (pintype "bidirectional"))
      (node (ref "R106") (pin "P$2") (pinfunction "P$2_P$2") (pintype "bidirectional"))
      (node (ref "R206") (pin "P$2") (pinfunction "P$2_P$2") (pintype "bidirectional"))
      (node (ref "R209") (pin "P$1") (pinfunction "P$1_P$1") (pintype "bidirectional"))
      (node (ref "R210") (pin "P$1") (pinfunction "P$1_P$1") (pintype "bidirectional"))
      (node (ref "R316") (pin "P$2") (pinfunction "P$2_P$2") (pintype "bidirectional"))
      (node (ref "R326") (pin "P$2") (pinfunction "P$2_P$2") (pintype "bidirectional"))
      (node (ref "U101") (pin "17") (pinfunction "IOVDD0_17") (pintype "bidirectional"))
      (node (ref "U101") (pin "31") (pinfunction "IOVDD0_31") (pintype "bidirectional"))
      (node (ref "U101") (pin "41") (pinfunction "AVDD_41") (pintype "bidirectional"))
      (node (ref "U101") (pin "44") (pinfunction "IOVDD0_44") (pintype "bidirectional"))
      (node (ref "U101") (pin "57") (pinfunction "VREGVDD_57") (pintype "bidirectional"))
      (node (ref "U101") (pin "73") (pinfunction "VREGO_73") (pintype "bidirectional"))
      (node (ref "U101") (pin "8") (pinfunction "IOVDD0_8") (pintype "bidirectional"))
      (node (ref "U101") (pin "82") (pinfunction "IOVDD0_82") (pintype "bidirectional"))
      (node (ref "U102") (pin "8") (pinfunction "VCC_8") (pintype "power_in"))
      (node (ref "U201") (pin "5") (pinfunction "VCC_5") (pintype "bidirectional"))
      (node (ref "U204") (pin "35") (pinfunction "~{RD}_35") (pintype "bidirectional"))
      (node (ref "U204") (pin "40") (pinfunction "VDDI_40") (pintype "bidirectional"))
      (node (ref "U204") (pin "41") (pinfunction "VDDI_41") (pintype "bidirectional"))
      (node (ref "U204") (pin "42") (pinfunction "VCI_42") (pintype "bidirectional"))
      (node (ref "U204") (pin "7") (pinfunction "IM0_7") (pintype "bidirectional"))
      (node (ref "U204") (pin "8") (pinfunction "IM1_8") (pintype "bidirectional"))
      (node (ref "U204") (pin "9") (pinfunction "IM2_9") (pintype "bidirectional"))
      (node (ref "U205") (pin "5") (pinfunction "VIO_5") (pintype "bidirectional"))
      (node (ref "U205") (pin "6") (pinfunction "VDD_6") (pintype "bidirectional"))
      (node (ref "U205") (pin "7") (pinfunction "VREGIN_7") (pintype "bidirectional"))
      (node (ref "U301") (pin "8") (pinfunction "VDD_8") (pintype "bidirectional"))
      (node (ref "U302") (pin "16") (pinfunction "ADDR_16") (pintype "bidirectional"))
      (node (ref "U302") (pin "8") (pinfunction "VDD_8") (pintype "bidirectional"))
    )
    (net (code "2") (name "5V") (class "Default")
      (node (ref "C108") (pin "P$1") (pinfunction "P$1_P$1") (pintype "bidirectional"))
      (node (ref "C203") (pin "P$1") (pinfunction "P$1_P$1") (pintype "bidirectional"))
      (node (ref "C204") (pin "P$1") (pinfunction "P$1_P$1") (pintype "bidirectional"))
      (node (ref "C404") (pin "+") (pinfunction "AN_+") (pintype "bidirectional"))
      (node (ref "C405") (pin "P$1") (pinfunction "P$1_P$1") (pintype "bidirectional"))
      (node (ref "D201") (pin "3") (pinfunction "VDD_3") (pintype "bidirectional"))
      (node (ref "D202") (pin "3") (pinfunction "VDD_3") (pintype "bidirectional"))
      (node (ref "D203") (pin "3") (pinfunction "VDD_3") (pintype "bidirectional"))
      (node (ref "D204") (pin "3") (pinfunction "VDD_3") (pintype "bidirectional"))
      (node (ref "D205") (pin "3") (pinfunction "VDD_3") (pintype "bidirectional"))
      (node (ref "J302") (pin "P$2") (pinfunction "S_P$2") (pintype "passive"))
      (node (ref "J303") (pin "P$2") (pinfunction "S_P$2") (pintype "passive"))
      (node (ref "L401") (pin "2") (pinfunction "P$2_2") (pintype "bidirectional"))
      (node (ref "R201") (pin "P$1") (pinfunction "P$1_P$1") (pintype "bidirectional"))
      (node (ref "R202") (pin "P$1") (pinfunction "P$1_P$1") (pintype "bidirectional"))
      (node (ref "R302") (pin "P$2") (pinfunction "P$2_P$2") (pintype "bidirectional"))
      (node (ref "R304") (pin "P$2") (pinfunction "P$2_P$2") (pintype "bidirectional"))
      (node (ref "R306") (pin "P$1") (pinfunction "P$1_P$1") (pintype "bidirectional"))
      (node (ref "R307") (pin "P$2") (pinfunction "P$2_P$2") (pintype "bidirectional"))
      (node (ref "R403") (pin "P$2") (pinfunction "P$2_P$2") (pintype "bidirectional"))
      (node (ref "U101") (pin "72") (pinfunction "VREGI_72") (pintype "bidirectional"))
      (node (ref "U101") (pin "79") (pinfunction "VBUS_79") (pintype "bidirectional"))
      (node (ref "U202") (pin "11") (pinfunction "~{RD}_11") (pintype "bidirectional"))
      (node (ref "U202") (pin "16") (pinfunction "VCC_16") (pintype "bidirectional"))
      (node (ref "U202") (pin "3") (pinfunction "~{RD}_3") (pintype "bidirectional"))
      (node (ref "U203") (pin "5") (pinfunction "VCC_5") (pintype "bidirectional"))
      (node (ref "U204") (pin "1") (pinfunction "LEDA_1") (pintype "bidirectional"))
    )
    (net (code "3") (name "12V") (class "Default")
      (node (ref "C401") (pin "P$1") (pinfunction "P$1_P$1") (pintype "bidirectional"))
      (node (ref "C402") (pin "+") (pinfunction "AN_+") (pintype "bidirectional"))
      (node (ref "F401") (pin "P$1") (pinfunction "1_P$1") (pintype "passive"))
      (node (ref "J306") (pin "2") (pinfunction "S_2") (pintype "passive"))
      (node (ref "J308") (pin "2") (pinfunction "S_2") (pintype "passive"))
      (node (ref "R213") (pin "P$2") (pinfunction "P$2_P$2") (pintype "bidirectional"))
      (node (ref "R214") (pin "P$2") (pinfunction "P$2_P$2") (pintype "bidirectional"))
      (node (ref "R321") (pin "P$2") (pinfunction "P$2_P$2") (pintype "bidirectional"))
      (node (ref "R328") (pin "P$2") (pinfunction "P$2_P$2") (pintype "bidirectional"))
      (node (ref "R401") (pin "P$2") (pinfunction "P$2_P$2") (pintype "bidirectional"))
      (node (ref "R405") (pin "P$2") (pinfunction "P$2_P$2") (pintype "bidirectional"))
      (node (ref "U401") (pin "5") (pinfunction "IN_5") (pintype "bidirectional"))
    )
    (net (code "4") (name "12V-FB") (class "Default")
      (node (ref "C403") (pin "P$1") (pinfunction "P$1_P$1") (pintype "bidirectional"))
      (node (ref "R405") (pin "P$1") (pinfunction "P$1_P$1") (pintype "bidirectional"))
      (node (ref "R406") (pin "P$2") (pinfunction "P$2_P$2") (pintype "bidirectional"))
      (node (ref "U101") (pin "45") (pinfunction "PD0_45") (pintype "bidirectional"))
    )
    (net (code "5") (name "AC-L") (class "Default")
      (node (ref "ACDC401") (pin "AC2") (pinfunction "AC2_AC2") (pintype "bidirectional"))
      (node (ref "J305") (pin "P$1") (pinfunction "S_P$1") (pintype "passive"))
      (node (ref "J401") (pin "P$2") (pinfunction "S_P$2") (pintype "passive"))
      (node (ref "R308") (pin "1") (pinfunction "P$1_1") (pintype "bidirectional"))
    )
    (net (code "6") (name "AC-N") (class "Default")
      (node (ref "ACDC401") (pin "AC1") (pinfunction "AC1_AC1") (pintype "bidirectional"))
      (node (ref "D302") (pin "A1") (pinfunction "A1_A1") (pintype "passive"))
      (node (ref "J401") (pin "P$1") (pinfunction "S_P$1") (pintype "passive"))
      (node (ref "R309") (pin "1") (pinfunction "P$1_1") (pintype "bidirectional"))
    )
    (net (code "7") (name "BLE-KEY") (class "Default")
      (node (ref "M201") (pin "16") (pinfunction "PIO0_16") (pintype "bidirectional"))
      (node (ref "U101") (pin "61") (pinfunction "PE1_61") (pintype "bidirectional"))
    )
    (net (code "8") (name "BLE-~{RST}") (class "Default")
      (node (ref "M201") (pin "11") (pinfunction "~{RST}_11") (pintype "bidirectional"))
      (node (ref "U101") (pin "53") (pinfunction "PD8_53") (pintype "bidirectional"))
    )
    (net (code "9") (name "DOOR-SW") (class "Default")
      (node (ref "C303") (pin "P$1") (pinfunction "P$1_P$1") (pintype "bidirectional"))
      (node (ref "R323") (pin "P$2") (pinfunction "P$2_P$2") (pintype "bidirectional"))
      (node (ref "U101") (pin "54") (pinfunction "PC7_54") (pintype "bidirectional"))
    )
    (net (code "10") (name "GND") (class "Default")
      (node (ref "ACDC401") (pin "-VO") (pinfunction "-VO_-VO") (pintype "bidirectional"))
      (node (ref "C101") (pin "P$2") (pinfunction "P$2_P$2") (pintype "bidirectional"))
      (node (ref "C102") (pin "P$2") (pinfunction "P$2_P$2") (pintype "bidirectional"))
      (node (ref "C103") (pin "P$2") (pinfunction "P$2_P$2") (pintype "bidirectional"))
      (node (ref "C104") (pin "P$2") (pinfunction "P$2_P$2") (pintype "bidirectional"))
      (node (ref "C105") (pin "P$2") (pinfunction "P$2_P$2") (pintype "bidirectional"))
      (node (ref "C106") (pin "P$2") (pinfunction "P$2_P$2") (pintype "bidirectional"))
      (node (ref "C107") (pin "P$2") (pinfunction "P$2_P$2") (pintype "bidirectional"))
      (node (ref "C108") (pin "P$2") (pinfunction "P$2_P$2") (pintype "bidirectional"))
      (node (ref "C109") (pin "P$2") (pinfunction "P$2_P$2") (pintype "bidirectional"))
      (node (ref "C110") (pin "P$2") (pinfunction "P$2_P$2") (pintype "bidirectional"))
      (node (ref "C111") (pin "P$2") (pinfunction "P$2_P$2") (pintype "bidirectional"))
      (node (ref "C203") (pin "P$2") (pinfunction "P$2_P$2") (pintype "bidirectional"))
      (node (ref "C204") (pin "P$2") (pinfunction "P$2_P$2") (pintype "bidirectional"))
      (node (ref "C205") (pin "P$2") (pinfunction "P$2_P$2") (pintype "bidirectional"))
      (node (ref "C206") (pin "P$2") (pinfunction "P$2_P$2") (pintype "bidirectional"))
      (node (ref "C207") (pin "P$2") (pinfunction "P$2_P$2") (pintype "bidirectional"))
      (node (ref "C208") (pin "P$2") (pinfunction "P$2_P$2") (pintype "bidirectional"))
      (node (ref "C209") (pin "P$2") (pinfunction "P$2_P$2") (pintype "bidirectional"))
      (node (ref "C301") (pin "P$2") (pinfunction "P$2_P$2") (pintype "bidirectional"))
      (node (ref "C302") (pin "P$2") (pinfunction "P$2_P$2") (pintype "bidirectional"))
      (node (ref "C303") (pin "P$2") (pinfunction "P$2_P$2") (pintype "bidirectional"))
      (node (ref "C401") (pin "P$2") (pinfunction "P$2_P$2") (pintype "bidirectional"))
      (node (ref "C402") (pin "-") (pinfunction "CA_-") (pintype "bidirectional"))
      (node (ref "C403") (pin "P$2") (pinfunction "P$2_P$2") (pintype "bidirectional"))
      (node (ref "C404") (pin "-") (pinfunction "CA_-") (pintype "bidirectional"))
      (node (ref "C405") (pin "P$2") (pinfunction "P$2_P$2") (pintype "bidirectional"))
      (node (ref "D201") (pin "1") (pinfunction "VSS_1") (pintype "bidirectional"))
      (node (ref "D202") (pin "1") (pinfunction "VSS_1") (pintype "bidirectional"))
      (node (ref "D203") (pin "1") (pinfunction "VSS_1") (pintype "bidirectional"))
      (node (ref "D204") (pin "1") (pinfunction "VSS_1") (pintype "bidirectional"))
      (node (ref "D205") (pin "1") (pinfunction "VSS_1") (pintype "bidirectional"))
      (node (ref "D206") (pin "1") (pinfunction "1_1") (pintype "bidirectional"))
      (node (ref "D208") (pin "C") (pinfunction "CA_C") (pintype "bidirectional"))
      (node (ref "D401") (pin "A") (pinfunction "A_A") (pintype "bidirectional"))
      (node (ref "J101") (pin "6") (pinfunction "6_6") (pintype "bidirectional"))
      (node (ref "J101") (pin "BODY1") (pinfunction "BODY_BODY1") (pintype "bidirectional"))
      (node (ref "J101") (pin "BODY2") (pinfunction "BODY_BODY2") (pintype "bidirectional"))
      (node (ref "J101") (pin "BODY3") (pinfunction "BODY_BODY3") (pintype "bidirectional"))
      (node (ref "J101") (pin "BODY4") (pinfunction "BODY_BODY4") (pintype "bidirectional"))
      (node (ref "J102") (pin "6") (pinfunction "S_6") (pintype "passive"))
      (node (ref "J102") (pin "FIT@1") (pinfunction "S_FIT@1") (pintype "passive"))
      (node (ref "J102") (pin "FIT@2") (pinfunction "S_FIT@2") (pintype "passive"))
      (node (ref "J201") (pin "GND") (pinfunction "GND_GND") (pintype "bidirectional"))
      (node (ref "J201") (pin "GND@1") (pinfunction "CASE_GND@1") (pintype "bidirectional"))
      (node (ref "J201") (pin "GND@2") (pinfunction "CASE_GND@2") (pintype "bidirectional"))
      (node (ref "J201") (pin "GND@3") (pinfunction "CASE_GND@3") (pintype "bidirectional"))
      (node (ref "J201") (pin "GND@4") (pinfunction "CASE_GND@4") (pintype "bidirectional"))
      (node (ref "J301") (pin "3-BAR") (pinfunction "S_3-BAR") (pintype "passive"))
      (node (ref "J301") (pin "4-BAR") (pinfunction "S_4-BAR") (pintype "passive"))
      (node (ref "J302") (pin "P$3") (pinfunction "S_P$3") (pintype "passive"))
      (node (ref "J303") (pin "P$3") (pinfunction "S_P$3") (pintype "passive"))
      (node (ref "J304") (pin "3-BAR") (pinfunction "S_3-BAR") (pintype "passive"))
      (node (ref "J304") (pin "4-BAR") (pinfunction "S_4-BAR") (pintype "passive"))
      (node (ref "J307") (pin "2") (pinfunction "S_2") (pintype "passive"))
      (node (ref "M201") (pin "12") (pinfunction "GND_12") (pintype "bidirectional"))
      (node (ref "Q201") (pin "P$2") (pinfunction "EM2_P$2") (pintype "bidirectional"))
      (node (ref "Q202") (pin "P$2") (pinfunction "EM2_P$2") (pintype "bidirectional"))
      (node (ref "Q301") (pin "P$2") (pinfunction "EM2_P$2") (pintype "bidirectional"))
      (node (ref "Q302") (pin "P$2") (pinfunction "EM2_P$2") (pintype "bidirectional"))
      (node (ref "Q303") (pin "P$2") (pinfunction "EM2_P$2") (pintype "bidirectional"))
      (node (ref "Q305") (pin "P$2") (pinfunction "EM2_P$2") (pintype "bidirectional"))
      (node (ref "Q306") (pin "P$2") (pinfunction "EM2_P$2") (pintype "bidirectional"))
      (node (ref "Q307") (pin "P$2") (pinfunction "EM2_P$2") (pintype "bidirectional"))
      (node (ref "Q308") (pin "P$2") (pinfunction "EM2_P$2") (pintype "bidirectional"))
      (node (ref "R208") (pin "P$1") (pinfunction "P$1_P$1") (pintype "bidirectional"))
      (node (ref "R317") (pin "P$1") (pinfunction "P$1_P$1") (pintype "bidirectional"))
      (node (ref "R322") (pin "P$1") (pinfunction "P$1_P$1") (pintype "bidirectional"))
      (node (ref "R402") (pin "P$1") (pinfunction "P$1_P$1") (pintype "bidirectional"))
      (node (ref "R404") (pin "P$1") (pinfunction "P$1_P$1") (pintype "bidirectional"))
      (node (ref "R406") (pin "P$1") (pinfunction "P$1_P$1") (pintype "bidirectional"))
      (node (ref "SW101") (pin "3") (pinfunction "3_3") (pintype "passive"))
      (node (ref "SW101") (pin "4") (pinfunction "4_4") (pintype "passive"))
      (node (ref "U101") (pin "16") (pinfunction "VSS_16") (pintype "bidirectional"))
      (node (ref "U101") (pin "32") (pinfunction "VSS_32") (pintype "bidirectional"))
      (node (ref "U101") (pin "55") (pinfunction "VREGVSS_55") (pintype "bidirectional"))
      (node (ref "U101") (pin "59") (pinfunction "VSS_59") (pintype "bidirectional"))
      (node (ref "U101") (pin "83") (pinfunction "VSS_83") (pintype "bidirectional"))
      (node (ref "U102") (pin "4") (pinfunction "GND_4") (pintype "power_in"))
      (node (ref "U201") (pin "3") (pinfunction "GND_3") (pintype "bidirectional"))
      (node (ref "U202") (pin "8") (pinfunction "GND_8") (pintype "bidirectional"))
      (node (ref "U203") (pin "3") (pinfunction "GND_3") (pintype "bidirectional"))
      (node (ref "U204") (pin "11") (pinfunction "VSYNC_11") (pintype "bidirectional"))
      (node (ref "U204") (pin "12") (pinfunction "HSYNC_12") (pintype "bidirectional"))
      (node (ref "U204") (pin "13") (pinfunction "DOTCLK_13") (pintype "bidirectional"))
      (node (ref "U204") (pin "14") (pinfunction "DE_14") (pintype "bidirectional"))
      (node (ref "U204") (pin "15") (pinfunction "DB17_15") (pintype "bidirectional"))
      (node (ref "U204") (pin "16") (pinfunction "DB16_16") (pintype "bidirectional"))
      (node (ref "U204") (pin "17") (pinfunction "DB15_17") (pintype "bidirectional"))
      (node (ref "U204") (pin "18") (pinfunction "DB14_18") (pintype "bidirectional"))
      (node (ref "U204") (pin "19") (pinfunction "DB13_19") (pintype "bidirectional"))
      (node (ref "U204") (pin "20") (pinfunction "DB12_20") (pintype "bidirectional"))
      (node (ref "U204") (pin "21") (pinfunction "DB11_21") (pintype "bidirectional"))
      (node (ref "U204") (pin "22") (pinfunction "DB10_22") (pintype "bidirectional"))
      (node (ref "U204") (pin "23") (pinfunction "DB9_23") (pintype "bidirectional"))
      (node (ref "U204") (pin "24") (pinfunction "DB8_24") (pintype "bidirectional"))
      (node (ref "U204") (pin "25") (pinfunction "DB7_25") (pintype "bidirectional"))
      (node (ref "U204") (pin "26") (pinfunction "DB6_26") (pintype "bidirectional"))
      (node (ref "U204") (pin "27") (pinfunction "DB5_27") (pintype "bidirectional"))
      (node (ref "U204") (pin "28") (pinfunction "DB4_28") (pintype "bidirectional"))
      (node (ref "U204") (pin "29") (pinfunction "DB3_29") (pintype "bidirectional"))
      (node (ref "U204") (pin "30") (pinfunction "DB2_30") (pintype "bidirectional"))
      (node (ref "U204") (pin "31") (pinfunction "DB1_31") (pintype "bidirectional"))
      (node (ref "U204") (pin "32") (pinfunction "DB0_32") (pintype "bidirectional"))
      (node (ref "U204") (pin "39") (pinfunction "TE_39") (pintype "bidirectional"))
      (node (ref "U204") (pin "43") (pinfunction "GND_43") (pintype "bidirectional"))
      (node (ref "U204") (pin "48") (pinfunction "GND_48") (pintype "bidirectional"))
      (node (ref "U204") (pin "49") (pinfunction "GND_49") (pintype "bidirectional"))
      (node (ref "U204") (pin "50") (pinfunction "GND_50") (pintype "bidirectional"))
      (node (ref "U205") (pin "2") (pinfunction "GND_2") (pintype "bidirectional"))
      (node (ref "U205") (pin "PAD") (pinfunction "GND_PAD") (pintype "bidirectional"))
      (node (ref "U301") (pin "1") (pinfunction "GND_1") (pintype "bidirectional"))
      (node (ref "U301") (pin "10") (pinfunction "GND_10") (pintype "bidirectional"))
      (node (ref "U301") (pin "13") (pinfunction "GND_13") (pintype "bidirectional"))
      (node (ref "U301") (pin "16") (pinfunction "ADDR_16") (pintype "bidirectional"))
      (node (ref "U301") (pin "17") (pinfunction "GND_17") (pintype "bidirectional"))
      (node (ref "U301") (pin "18") (pinfunction "GND_18") (pintype "bidirectional"))
      (node (ref "U301") (pin "3") (pinfunction "GND_3") (pintype "bidirectional"))
      (node (ref "U301") (pin "5") (pinfunction "GND_5") (pintype "bidirectional"))
      (node (ref "U301") (pin "6") (pinfunction "GND_6") (pintype "bidirectional"))
      (node (ref "U301") (pin "7") (pinfunction "GND_7") (pintype "bidirectional"))
      (node (ref "U301") (pin "9") (pinfunction "GND_9") (pintype "bidirectional"))
      (node (ref "U301") (pin "EXP") (pinfunction "EP_EXP") (pintype "bidirectional"))
      (node (ref "U302") (pin "1") (pinfunction "GND_1") (pintype "bidirectional"))
      (node (ref "U302") (pin "10") (pinfunction "GND_10") (pintype "bidirectional"))
      (node (ref "U302") (pin "13") (pinfunction "GND_13") (pintype "bidirectional"))
      (node (ref "U302") (pin "17") (pinfunction "GND_17") (pintype "bidirectional"))
      (node (ref "U302") (pin "18") (pinfunction "GND_18") (pintype "bidirectional"))
      (node (ref "U302") (pin "3") (pinfunction "GND_3") (pintype "bidirectional"))
      (node (ref "U302") (pin "5") (pinfunction "GND_5") (pintype "bidirectional"))
      (node (ref "U302") (pin "6") (pinfunction "GND_6") (pintype "bidirectional"))
      (node (ref "U302") (pin "7") (pinfunction "GND_7") (pintype "bidirectional"))
      (node (ref "U302") (pin "9") (pinfunction "GND_9") (pintype "bidirectional"))
      (node (ref "U302") (pin "EXP") (pinfunction "EP_EXP") (pintype "bidirectional"))
      (node (ref "U303") (pin "P$4") (pinfunction "E_P$4") (pintype "bidirectional"))
      (node (ref "U401") (pin "2") (pinfunction "GND_2") (pintype "bidirectional"))
      (node (ref "U401") (pin "4") (pinfunction "SHDN_4") (pintype "bidirectional"))
      (node (ref "U401") (pin "6") (pinfunction "GND_6") (pintype "bidirectional"))
      (node (ref "U401") (pin "7") (pinfunction "GND_7") (pintype "bidirectional"))
    )
    (net (code "11") (name "I2C0-SCL-SENS") (class "Default")
      (node (ref "R102") (pin "P$1") (pinfunction "P$1_P$1") (pintype "bidirectional"))
      (node (ref "U101") (pin "52") (pinfunction "PD7_52") (pintype "bidirectional"))
      (node (ref "U301") (pin "19") (pinfunction "SCL_19") (pintype "bidirectional"))
      (node (ref "U302") (pin "19") (pinfunction "SCL_19") (pintype "bidirectional"))
    )
    (net (code "12") (name "I2C0-SDA-SENS") (class "Default")
      (node (ref "R101") (pin "P$1") (pinfunction "P$1_P$1") (pintype "bidirectional"))
      (node (ref "U101") (pin "51") (pinfunction "PD6_51") (pintype "bidirectional"))
      (node (ref "U301") (pin "20") (pinfunction "SDA_20") (pintype "bidirectional"))
      (node (ref "U302") (pin "20") (pinfunction "SDA_20") (pintype "bidirectional"))
    )
    (net (code "13") (name "I2C1-SCL-TTFT") (class "Default")
      (node (ref "R104") (pin "P$1") (pinfunction "P$1_P$1") (pintype "bidirectional"))
      (node (ref "U101") (pin "23") (pinfunction "PC5_23") (pintype "bidirectional"))
      (node (ref "U204") (pin "44") (pinfunction "X+/SCL_44") (pintype "bidirectional"))
    )
    (net (code "14") (name "I2C1-SDA-TTFT") (class "Default")
      (node (ref "R103") (pin "P$1") (pinfunction "P$1_P$1") (pintype "bidirectional"))
      (node (ref "U101") (pin "22") (pinfunction "PC4_22") (pintype "bidirectional"))
      (node (ref "U204") (pin "45") (pinfunction "Y+/SDA_45") (pintype "bidirectional"))
    )
    (net (code "15") (name "MAIN_HFXTAL_N") (class "Default")
      (node (ref "U101") (pin "43") (pinfunction "PB14_43") (pintype "bidirectional"))
      (node (ref "Y101") (pin "1") (pinfunction "1_1") (pintype "passive"))
    )
    (net (code "16") (name "MAIN_HFXTAL_P") (class "Default")
      (node (ref "U101") (pin "42") (pinfunction "PB13_42") (pintype "bidirectional"))
      (node (ref "Y101") (pin "2") (pinfunction "2_2") (pintype "passive"))
    )
    (net (code "17") (name "MAIN_LFXTAL_N") (class "Default")
      (node (ref "U101") (pin "25") (pinfunction "PB8_25") (pintype "bidirectional"))
      (node (ref "Y102") (pin "4") (pinfunction "2_4") (pintype "passive"))
    )
    (net (code "18") (name "MAIN_LFXTAL_P") (class "Default")
      (node (ref "U101") (pin "24") (pinfunction "PB7_24") (pintype "bidirectional"))
      (node (ref "Y102") (pin "1") (pinfunction "1_1") (pintype "passive"))
    )
    (net (code "19") (name "Net-(B201-A)") (class "Default")
      (node (ref "B201") (pin "1") (pinfunction "A_1") (pintype "bidirectional"))
      (node (ref "R214") (pin "P$1") (pinfunction "P$1_P$1") (pintype "bidirectional"))
    )
    (net (code "20") (name "Net-(B201-B)") (class "Default")
      (node (ref "B201") (pin "2") (pinfunction "B_2") (pintype "bidirectional"))
      (node (ref "Q202") (pin "P$3") (pinfunction "C03_P$3") (pintype "bidirectional"))
      (node (ref "R213") (pin "P$1") (pinfunction "P$1_P$1") (pintype "bidirectional"))
    )
    (net (code "21") (name "Net-(D201-DI)") (class "Default")
      (node (ref "D201") (pin "2") (pinfunction "DI_2") (pintype "bidirectional"))
      (node (ref "TP201") (pin "1") (pinfunction "S_1") (pintype "passive"))
      (node (ref "U203") (pin "4") (pinfunction "Y_4") (pintype "output"))
    )
    (net (code "22") (name "Net-(D201-DO)") (class "Default")
      (node (ref "D201") (pin "4") (pinfunction "DO_4") (pintype "bidirectional"))
      (node (ref "D202") (pin "2") (pinfunction "DI_2") (pintype "bidirectional"))
    )
    (net (code "23") (name "Net-(D202-DO)") (class "Default")
      (node (ref "D202") (pin "4") (pinfunction "DO_4") (pintype "bidirectional"))
      (node (ref "D203") (pin "2") (pinfunction "DI_2") (pintype "bidirectional"))
    )
    (net (code "24") (name "Net-(D203-DO)") (class "Default")
      (node (ref "D203") (pin "4") (pinfunction "DO_4") (pintype "bidirectional"))
      (node (ref "D204") (pin "2") (pinfunction "DI_2") (pintype "bidirectional"))
    )
    (net (code "25") (name "Net-(D204-DO)") (class "Default")
      (node (ref "D204") (pin "4") (pinfunction "DO_4") (pintype "bidirectional"))
      (node (ref "D205") (pin "2") (pinfunction "DI_2") (pintype "bidirectional"))
    )
    (net (code "26") (name "Net-(D206-Pad2)") (class "Default")
      (node (ref "D206") (pin "2") (pinfunction "2_2") (pintype "bidirectional"))
      (node (ref "J201") (pin "D-") (pinfunction "D-_D-") (pintype "bidirectional"))
      (node (ref "JP201") (pin "2") (pinfunction "2_2") (pintype "passive"))
    )
    (net (code "27") (name "Net-(D206-Pad3)") (class "Default")
      (node (ref "D206") (pin "3") (pinfunction "3_3") (pintype "bidirectional"))
      (node (ref "J201") (pin "D+") (pinfunction "D+_D+") (pintype "bidirectional"))
      (node (ref "JP202") (pin "2") (pinfunction "2_2") (pintype "passive"))
    )
    (net (code "28") (name "Net-(D207-AN)") (class "Default")
      (node (ref "D207") (pin "A") (pinfunction "AN_A") (pintype "bidirectional"))
      (node (ref "R209") (pin "P$2") (pinfunction "P$2_P$2") (pintype "bidirectional"))
    )
    (net (code "29") (name "Net-(D207-CA)") (class "Default")
      (node (ref "D207") (pin "C") (pinfunction "CA_C") (pintype "bidirectional"))
      (node (ref "U205") (pin "13") (pinfunction "GPIO1-RXT_13") (pintype "bidirectional"))
    )
    (net (code "30") (name "Net-(D208-AN)") (class "Default")
      (node (ref "D208") (pin "A") (pinfunction "AN_A") (pintype "bidirectional"))
      (node (ref "R211") (pin "P$2") (pinfunction "P$2_P$2") (pintype "bidirectional"))
    )
    (net (code "31") (name "Net-(D209-AN)") (class "Default")
      (node (ref "D209") (pin "A") (pinfunction "AN_A") (pintype "bidirectional"))
      (node (ref "R210") (pin "P$2") (pinfunction "P$2_P$2") (pintype "bidirectional"))
    )
    (net (code "32") (name "Net-(D209-CA)") (class "Default")
      (node (ref "D209") (pin "C") (pinfunction "CA_C") (pintype "bidirectional"))
      (node (ref "U205") (pin "14") (pinfunction "GPIO0-TXT_14") (pintype "bidirectional"))
    )
    (net (code "33") (name "Net-(D301-AN)") (class "Default")
      (node (ref "D301") (pin "A") (pinfunction "AN_A") (pintype "bidirectional"))
      (node (ref "R306") (pin "P$2") (pinfunction "P$2_P$2") (pintype "bidirectional"))
    )
    (net (code "34") (name "Net-(D301-CA)") (class "Default")
      (node (ref "D301") (pin "C") (pinfunction "CA_C") (pintype "bidirectional"))
      (node (ref "Q303") (pin "P$3") (pinfunction "C03_P$3") (pintype "bidirectional"))
      (node (ref "Q304") (pin "P$2") (pinfunction "CA_P$2") (pintype "bidirectional"))
    )
    (net (code "35") (name "Net-(F401-2)") (class "Default")
      (node (ref "ACDC401") (pin "+VO") (pinfunction "+VO_+VO") (pintype "bidirectional"))
      (node (ref "F401") (pin "P$2") (pinfunction "2_P$2") (pintype "passive"))
    )
    (net (code "36") (name "Net-(J301B-S)") (class "Default")
      (node (ref "J301") (pin "1-T+") (pinfunction "S_1-T+") (pintype "passive"))
      (node (ref "U301") (pin "2") (pinfunction "VIN+_2") (pintype "bidirectional"))
    )
    (net (code "37") (name "Net-(J301C-S)") (class "Default")
      (node (ref "J301") (pin "2-T-") (pinfunction "S_2-T-") (pintype "passive"))
      (node (ref "U301") (pin "4") (pinfunction "VIN-_4") (pintype "bidirectional"))
    )
    (net (code "38") (name "Net-(J302A-S)") (class "Default")
      (node (ref "J302") (pin "P$1") (pinfunction "S_P$1") (pintype "passive"))
      (node (ref "Q301") (pin "P$3") (pinfunction "C03_P$3") (pintype "bidirectional"))
      (node (ref "R302") (pin "P$1") (pinfunction "P$1_P$1") (pintype "bidirectional"))
    )
    (net (code "39") (name "Net-(J303A-S)") (class "Default")
      (node (ref "J303") (pin "P$1") (pinfunction "S_P$1") (pintype "passive"))
      (node (ref "Q302") (pin "P$3") (pinfunction "C03_P$3") (pintype "bidirectional"))
      (node (ref "R304") (pin "P$1") (pinfunction "P$1_P$1") (pintype "bidirectional"))
    )
    (net (code "40") (name "Net-(J304B-S)") (class "Default")
      (node (ref "J304") (pin "1-T+") (pinfunction "S_1-T+") (pintype "passive"))
      (node (ref "U302") (pin "2") (pinfunction "VIN+_2") (pintype "bidirectional"))
    )
    (net (code "41") (name "Net-(J304C-S)") (class "Default")
      (node (ref "J304") (pin "2-T-") (pinfunction "S_2-T-") (pintype "passive"))
      (node (ref "U302") (pin "4") (pinfunction "VIN-_4") (pintype "bidirectional"))
    )
    (net (code "42") (name "Net-(J305B-S)") (class "Default")
      (node (ref "D302") (pin "A2") (pinfunction "A2_A2") (pintype "passive"))
      (node (ref "J305") (pin "P$2") (pinfunction "S_P$2") (pintype "passive"))
      (node (ref "R314") (pin "2") (pinfunction "P$2_2") (pintype "bidirectional"))
    )
    (net (code "43") (name "Net-(J306B-S)") (class "Default")
      (node (ref "J306") (pin "4") (pinfunction "S_4") (pintype "passive"))
      (node (ref "Q305") (pin "P$3") (pinfunction "C03_P$3") (pintype "bidirectional"))
      (node (ref "R321") (pin "P$1") (pinfunction "P$1_P$1") (pintype "bidirectional"))
    )
    (net (code "44") (name "Net-(J306C-S)") (class "Default")
      (node (ref "J306") (pin "1") (pinfunction "S_1") (pintype "passive"))
      (node (ref "Q306") (pin "P$3") (pinfunction "C03_P$3") (pintype "bidirectional"))
    )
    (net (code "45") (name "Net-(J306D-S)") (class "Default")
      (node (ref "J306") (pin "3") (pinfunction "S_3") (pintype "passive"))
      (node (ref "R320") (pin "P$2") (pinfunction "P$2_P$2") (pintype "bidirectional"))
    )
    (net (code "46") (name "Net-(J307A-S)") (class "Default")
      (node (ref "J307") (pin "1") (pinfunction "S_1") (pintype "passive"))
      (node (ref "R323") (pin "P$1") (pinfunction "P$1_P$1") (pintype "bidirectional"))
      (node (ref "R326") (pin "P$1") (pinfunction "P$1_P$1") (pintype "bidirectional"))
    )
    (net (code "47") (name "Net-(J308B-S)") (class "Default")
      (node (ref "J308") (pin "4") (pinfunction "S_4") (pintype "passive"))
      (node (ref "Q307") (pin "P$3") (pinfunction "C03_P$3") (pintype "bidirectional"))
      (node (ref "R328") (pin "P$1") (pinfunction "P$1_P$1") (pintype "bidirectional"))
    )
    (net (code "48") (name "Net-(J308C-S)") (class "Default")
      (node (ref "J308") (pin "1") (pinfunction "S_1") (pintype "passive"))
      (node (ref "Q308") (pin "P$3") (pinfunction "C03_P$3") (pintype "bidirectional"))
    )
    (net (code "49") (name "Net-(J308D-S)") (class "Default")
      (node (ref "J308") (pin "3") (pinfunction "S_3") (pintype "passive"))
      (node (ref "R327") (pin "P$2") (pinfunction "P$2_P$2") (pintype "bidirectional"))
    )
    (net (code "50") (name "Net-(L101-P$1)") (class "Default")
      (node (ref "C107") (pin "P$1") (pinfunction "P$1_P$1") (pintype "bidirectional"))
      (node (ref "L101") (pin "1") (pinfunction "P$1_1") (pintype "bidirectional"))
      (node (ref "U101") (pin "58") (pinfunction "DVDD_58") (pintype "bidirectional"))
    )
    (net (code "51") (name "Net-(L101-P$2)") (class "Default")
      (node (ref "L101") (pin "2") (pinfunction "P$2_2") (pintype "bidirectional"))
      (node (ref "U101") (pin "56") (pinfunction "VREGSW_56") (pintype "bidirectional"))
    )
    (net (code "52") (name "Net-(L401-P$1)") (class "Default")
      (node (ref "D401") (pin "C") (pinfunction "C_C") (pintype "bidirectional"))
      (node (ref "L401") (pin "1") (pinfunction "P$1_1") (pintype "bidirectional"))
      (node (ref "U401") (pin "8") (pinfunction "SW_8") (pintype "bidirectional"))
    )
    (net (code "53") (name "Net-(M201-PIO1)") (class "Default")
      (node (ref "M201") (pin "15") (pinfunction "PIO1_15") (pintype "bidirectional"))
      (node (ref "R211") (pin "P$1") (pinfunction "P$1_P$1") (pintype "bidirectional"))
    )
    (net (code "54") (name "Net-(Q201-BA1)") (class "Default")
      (node (ref "Q201") (pin "P$1") (pinfunction "BA1_P$1") (pintype "bidirectional"))
      (node (ref "R203") (pin "P$2") (pinfunction "P$2_P$2") (pintype "bidirectional"))
    )
    (net (code "55") (name "Net-(Q201-C03)") (class "Default")
      (node (ref "Q201") (pin "P$3") (pinfunction "C03_P$3") (pintype "bidirectional"))
      (node (ref "R204") (pin "P$1") (pinfunction "P$1_P$1") (pintype "bidirectional"))
      (node (ref "R205") (pin "P$1") (pinfunction "P$1_P$1") (pintype "bidirectional"))
    )
    (net (code "56") (name "Net-(Q202-BA1)") (class "Default")
      (node (ref "Q202") (pin "P$1") (pinfunction "BA1_P$1") (pintype "bidirectional"))
      (node (ref "R212") (pin "P$2") (pinfunction "P$2_P$2") (pintype "bidirectional"))
    )
    (net (code "57") (name "Net-(Q301-BA1)") (class "Default")
      (node (ref "Q301") (pin "P$1") (pinfunction "BA1_P$1") (pintype "bidirectional"))
      (node (ref "R301") (pin "P$2") (pinfunction "P$2_P$2") (pintype "bidirectional"))
    )
    (net (code "58") (name "Net-(Q302-BA1)") (class "Default")
      (node (ref "Q302") (pin "P$1") (pinfunction "BA1_P$1") (pintype "bidirectional"))
      (node (ref "R303") (pin "P$2") (pinfunction "P$2_P$2") (pintype "bidirectional"))
    )
    (net (code "59") (name "Net-(Q303-BA1)") (class "Default")
      (node (ref "Q303") (pin "P$1") (pinfunction "BA1_P$1") (pintype "bidirectional"))
      (node (ref "R305") (pin "P$2") (pinfunction "P$2_P$2") (pintype "bidirectional"))
    )
    (net (code "60") (name "Net-(Q304-AN)") (class "Default")
      (node (ref "Q304") (pin "P$1") (pinfunction "AN_P$1") (pintype "bidirectional"))
      (node (ref "R307") (pin "P$1") (pinfunction "P$1_P$1") (pintype "bidirectional"))
    )
    (net (code "61") (name "Net-(Q305-BA1)") (class "Default")
      (node (ref "Q305") (pin "P$1") (pinfunction "BA1_P$1") (pintype "bidirectional"))
      (node (ref "R318") (pin "P$2") (pinfunction "P$2_P$2") (pintype "bidirectional"))
    )
    (net (code "62") (name "Net-(Q306-BA1)") (class "Default")
      (node (ref "Q306") (pin "P$1") (pinfunction "BA1_P$1") (pintype "bidirectional"))
      (node (ref "R319") (pin "P$2") (pinfunction "P$2_P$2") (pintype "bidirectional"))
    )
    (net (code "63") (name "Net-(Q307-BA1)") (class "Default")
      (node (ref "Q307") (pin "P$1") (pinfunction "BA1_P$1") (pintype "bidirectional"))
      (node (ref "R324") (pin "P$2") (pinfunction "P$2_P$2") (pintype "bidirectional"))
    )
    (net (code "64") (name "Net-(Q308-BA1)") (class "Default")
      (node (ref "Q308") (pin "P$1") (pinfunction "BA1_P$1") (pintype "bidirectional"))
      (node (ref "R325") (pin "P$2") (pinfunction "P$2_P$2") (pintype "bidirectional"))
    )
    (net (code "65") (name "Net-(R204-PadP$2)") (class "Default")
      (node (ref "R204") (pin "P$2") (pinfunction "P$2_P$2") (pintype "bidirectional"))
      (node (ref "U204") (pin "2") (pinfunction "LEDK_2") (pintype "bidirectional"))
    )
    (net (code "66") (name "Net-(R205-PadP$2)") (class "Default")
      (node (ref "R205") (pin "P$2") (pinfunction "P$2_P$2") (pintype "bidirectional"))
      (node (ref "U204") (pin "3") (pinfunction "LEDK_3") (pintype "bidirectional"))
    )
    (net (code "67") (name "Net-(R308-P$2)") (class "Default")
      (node (ref "R308") (pin "2") (pinfunction "P$2_2") (pintype "bidirectional"))
      (node (ref "R310") (pin "1") (pinfunction "P$1_1") (pintype "bidirectional"))
    )
    (net (code "68") (name "Net-(R309-P$2)") (class "Default")
      (node (ref "R309") (pin "2") (pinfunction "P$2_2") (pintype "bidirectional"))
      (node (ref "R311") (pin "1") (pinfunction "P$1_1") (pintype "bidirectional"))
    )
    (net (code "69") (name "Net-(R310-P$2)") (class "Default")
      (node (ref "R310") (pin "2") (pinfunction "P$2_2") (pintype "bidirectional"))
      (node (ref "U303") (pin "P$1") (pinfunction "AC_P$1") (pintype "bidirectional"))
    )
    (net (code "70") (name "Net-(R311-P$2)") (class "Default")
      (node (ref "R311") (pin "2") (pinfunction "P$2_2") (pintype "bidirectional"))
      (node (ref "U303") (pin "P$2") (pinfunction "CA_P$2") (pintype "bidirectional"))
    )
    (net (code "71") (name "Net-(R312-P$1)") (class "Default")
      (node (ref "Q304") (pin "P$4") (pinfunction "MAIN_P$4") (pintype "bidirectional"))
      (node (ref "R312") (pin "1") (pinfunction "P$1_1") (pintype "bidirectional"))
    )
    (net (code "72") (name "Net-(R312-P$2)") (class "Default")
      (node (ref "R312") (pin "2") (pinfunction "P$2_2") (pintype "bidirectional"))
      (node (ref "R314") (pin "1") (pinfunction "P$1_1") (pintype "bidirectional"))
    )
    (net (code "73") (name "Net-(R313-P$1)") (class "Default")
      (node (ref "Q304") (pin "P$6") (pinfunction "MAIN_P$6") (pintype "bidirectional"))
      (node (ref "R313") (pin "1") (pinfunction "P$1_1") (pintype "bidirectional"))
    )
    (net (code "74") (name "Net-(R313-P$2)") (class "Default")
      (node (ref "R313") (pin "2") (pinfunction "P$2_2") (pintype "bidirectional"))
      (node (ref "R315") (pin "1") (pinfunction "P$1_1") (pintype "bidirectional"))
    )
    (net (code "75") (name "Net-(R315-P$2)") (class "Default")
      (node (ref "D302") (pin "G") (pinfunction "G_G") (pintype "passive"))
      (node (ref "R315") (pin "2") (pinfunction "P$2_2") (pintype "bidirectional"))
    )
    (net (code "76") (name "Net-(TP1-S)") (class "Default")
      (node (ref "TP1") (pin "1") (pinfunction "S_1") (pintype "passive"))
      (node (ref "U101") (pin "1") (pinfunction "PA0_1") (pintype "bidirectional"))
    )
    (net (code "77") (name "Net-(TP2-S)") (class "Default")
      (node (ref "TP2") (pin "1") (pinfunction "S_1") (pintype "passive"))
      (node (ref "U101") (pin "6") (pinfunction "PA5_6") (pintype "bidirectional"))
    )
    (net (code "78") (name "Net-(TP3-S)") (class "Default")
      (node (ref "TP3") (pin "1") (pinfunction "S_1") (pintype "passive"))
      (node (ref "U101") (pin "28") (pinfunction "PA9_28") (pintype "bidirectional"))
    )
    (net (code "79") (name "Net-(TP4-S)") (class "Default")
      (node (ref "TP4") (pin "1") (pinfunction "S_1") (pintype "passive"))
      (node (ref "U101") (pin "29") (pinfunction "PA10_29") (pintype "bidirectional"))
    )
    (net (code "80") (name "Net-(TP5-S)") (class "Default")
      (node (ref "TP5") (pin "1") (pinfunction "S_1") (pintype "passive"))
      (node (ref "U101") (pin "30") (pinfunction "PA11_30") (pintype "bidirectional"))
    )
    (net (code "81") (name "Net-(TP6-S)") (class "Default")
      (node (ref "TP6") (pin "1") (pinfunction "S_1") (pintype "passive"))
      (node (ref "U101") (pin "33") (pinfunction "PA12_33") (pintype "bidirectional"))
    )
    (net (code "82") (name "Net-(TP7-S)") (class "Default")
      (node (ref "TP7") (pin "1") (pinfunction "S_1") (pintype "passive"))
      (node (ref "U101") (pin "34") (pinfunction "PA13_34") (pintype "bidirectional"))
    )
    (net (code "83") (name "Net-(TP8-S)") (class "Default")
      (node (ref "TP8") (pin "1") (pinfunction "S_1") (pintype "passive"))
      (node (ref "U101") (pin "35") (pinfunction "PA14_35") (pintype "bidirectional"))
    )
    (net (code "84") (name "Net-(TP9-S)") (class "Default")
      (node (ref "TP9") (pin "1") (pinfunction "S_1") (pintype "passive"))
      (node (ref "U101") (pin "100") (pinfunction "PA15_100") (pintype "bidirectional"))
    )
    (net (code "85") (name "Net-(TP10-S)") (class "Default")
      (node (ref "TP10") (pin "1") (pinfunction "S_1") (pintype "passive"))
      (node (ref "U101") (pin "71") (pinfunction "PC11_71") (pintype "bidirectional"))
    )
    (net (code "86") (name "Net-(TP11-S)") (class "Default")
      (node (ref "TP11") (pin "1") (pinfunction "S_1") (pintype "passive"))
      (node (ref "U101") (pin "98") (pinfunction "PE14_98") (pintype "bidirectional"))
    )
    (net (code "87") (name "Net-(TP12-S)") (class "Default")
      (node (ref "TP12") (pin "1") (pinfunction "S_1") (pintype "passive"))
      (node (ref "U101") (pin "99") (pinfunction "PE15_99") (pintype "bidirectional"))
    )
    (net (code "88") (name "Net-(TP13-S)") (class "Default")
      (node (ref "TP13") (pin "1") (pinfunction "S_1") (pintype "passive"))
      (node (ref "U101") (pin "87") (pinfunction "PF9_87") (pintype "bidirectional"))
    )
    (net (code "89") (name "Net-(TP14-S)") (class "Default")
      (node (ref "TP14") (pin "1") (pinfunction "S_1") (pintype "passive"))
      (node (ref "U101") (pin "81") (pinfunction "PF5_81") (pintype "bidirectional"))
    )
    (net (code "90") (name "Net-(TP15-S)") (class "Default")
      (node (ref "TP15") (pin "1") (pinfunction "S_1") (pintype "passive"))
      (node (ref "U101") (pin "40") (pinfunction "PB12_40") (pintype "bidirectional"))
    )
    (net (code "91") (name "Net-(TP16-S)") (class "Default")
      (node (ref "TP16") (pin "1") (pinfunction "S_1") (pintype "passive"))
      (node (ref "U101") (pin "39") (pinfunction "PB11_39") (pintype "bidirectional"))
    )
    (net (code "92") (name "Net-(TP17-S)") (class "Default")
      (node (ref "TP17") (pin "1") (pinfunction "S_1") (pintype "passive"))
      (node (ref "U101") (pin "38") (pinfunction "PB10_38") (pintype "bidirectional"))
    )
    (net (code "93") (name "Net-(TP18-S)") (class "Default")
      (node (ref "TP18") (pin "1") (pinfunction "S_1") (pintype "passive"))
      (node (ref "U101") (pin "37") (pinfunction "PB9_37") (pintype "bidirectional"))
    )
    (net (code "94") (name "Net-(TP19-S)") (class "Default")
      (node (ref "TP19") (pin "1") (pinfunction "S_1") (pintype "passive"))
      (node (ref "U101") (pin "13") (pinfunction "PB4_13") (pintype "bidirectional"))
    )
    (net (code "95") (name "Net-(TP20-S)") (class "Default")
      (node (ref "TP20") (pin "1") (pinfunction "S_1") (pintype "passive"))
      (node (ref "U101") (pin "11") (pinfunction "PB2_11") (pintype "bidirectional"))
    )
    (net (code "96") (name "Net-(TP21-S)") (class "Default")
      (node (ref "TP21") (pin "1") (pinfunction "S_1") (pintype "passive"))
      (node (ref "U101") (pin "10") (pinfunction "PB1_10") (pintype "bidirectional"))
    )
    (net (code "97") (name "Net-(TP22-S)") (class "Default")
      (node (ref "TP22") (pin "1") (pinfunction "S_1") (pintype "passive"))
      (node (ref "U301") (pin "11") (pinfunction "ALRT1_11") (pintype "bidirectional"))
    )
    (net (code "98") (name "Net-(TP26-S)") (class "Default")
      (node (ref "TP26") (pin "1") (pinfunction "S_1") (pintype "passive"))
      (node (ref "U302") (pin "11") (pinfunction "ALRT1_11") (pintype "bidirectional"))
    )
    (net (code "99") (name "Net-(U101-DECOUPLE)") (class "Default")
      (node (ref "C109") (pin "P$1") (pinfunction "P$1_P$1") (pintype "bidirectional"))
      (node (ref "U101") (pin "60") (pinfunction "DECOUPLE_60") (pintype "bidirectional"))
    )
    (net (code "100") (name "Net-(U201A-Y)") (class "Default")
      (node (ref "U201") (pin "4") (pinfunction "Y_4") (pintype "output"))
      (node (ref "U202") (pin "2") (pinfunction "B_2") (pintype "bidirectional"))
    )
    (net (code "101") (name "Net-(U202A-C)") (class "Default")
      (node (ref "C201") (pin "P$1") (pinfunction "P$1_P$1") (pintype "bidirectional"))
      (node (ref "U202") (pin "14") (pinfunction "C_14") (pintype "bidirectional"))
    )
    (net (code "102") (name "Net-(U202A-Q)") (class "Default")
      (node (ref "U202") (pin "13") (pinfunction "Q_13") (pintype "bidirectional"))
      (node (ref "U203") (pin "2") (pinfunction "A_2") (pintype "input"))
    )
    (net (code "103") (name "Net-(U202A-R{slash}C)") (class "Default")
      (node (ref "C201") (pin "P$2") (pinfunction "P$2_P$2") (pintype "bidirectional"))
      (node (ref "R201") (pin "P$2") (pinfunction "P$2_P$2") (pintype "bidirectional"))
      (node (ref "U202") (pin "15") (pinfunction "R/C_15") (pintype "bidirectional"))
    )
    (net (code "104") (name "Net-(U202B-C)") (class "Default")
      (node (ref "C202") (pin "P$1") (pinfunction "P$1_P$1") (pintype "bidirectional"))
      (node (ref "U202") (pin "6") (pinfunction "C_6") (pintype "bidirectional"))
    )
    (net (code "105") (name "Net-(U202B-Q)") (class "Default")
      (node (ref "U202") (pin "5") (pinfunction "Q_5") (pintype "bidirectional"))
      (node (ref "U203") (pin "1") (pinfunction "B_1") (pintype "input"))
    )
    (net (code "106") (name "Net-(U202B-R{slash}C)") (class "Default")
      (node (ref "C202") (pin "P$2") (pinfunction "P$2_P$2") (pintype "bidirectional"))
      (node (ref "R202") (pin "P$2") (pinfunction "P$2_P$2") (pintype "bidirectional"))
      (node (ref "U202") (pin "7") (pinfunction "R/C_7") (pintype "bidirectional"))
    )
    (net (code "107") (name "Net-(U401-FB)") (class "Default")
      (node (ref "R403") (pin "P$1") (pinfunction "P$1_P$1") (pintype "bidirectional"))
      (node (ref "R404") (pin "P$2") (pinfunction "P$2_P$2") (pintype "bidirectional"))
      (node (ref "U401") (pin "1") (pinfunction "FB_1") (pintype "bidirectional"))
    )
    (net (code "108") (name "Net-(U401-ISET)") (class "Default")
      (node (ref "R401") (pin "P$1") (pinfunction "P$1_P$1") (pintype "bidirectional"))
      (node (ref "R402") (pin "P$2") (pinfunction "P$2_P$2") (pintype "bidirectional"))
      (node (ref "U401") (pin "3") (pinfunction "ISET_3") (pintype "bidirectional"))
    )
    (net (code "109") (name "PRS-CH11-SSR-OUT") (class "Default")
      (node (ref "R305") (pin "P$1") (pinfunction "P$1_P$1") (pintype "bidirectional"))
      (node (ref "TP301") (pin "1") (pinfunction "S_1") (pintype "passive"))
      (node (ref "U101") (pin "50") (pinfunction "PD5_50") (pintype "bidirectional"))
    )
    (net (code "110") (name "QSPI_CLK") (class "Default")
      (node (ref "U101") (pin "84") (pinfunction "PF6_84") (pintype "bidirectional"))
      (node (ref "U102") (pin "6") (pinfunction "SCK_6") (pintype "input"))
    )
    (net (code "111") (name "QSPI_CS0") (class "Default")
      (node (ref "R105") (pin "P$1") (pinfunction "P$1_P$1") (pintype "bidirectional"))
      (node (ref "U101") (pin "85") (pinfunction "PF7_85") (pintype "bidirectional"))
      (node (ref "U102") (pin "1") (pinfunction "~{CS}_1") (pintype "input"))
    )
    (net (code "112") (name "QSPI_D0") (class "Default")
      (node (ref "U101") (pin "88") (pinfunction "PD9_88") (pintype "bidirectional"))
      (node (ref "U102") (pin "5") (pinfunction "MOSI/IO0_5") (pintype "input"))
    )
    (net (code "113") (name "QSPI_D1") (class "Default")
      (node (ref "U101") (pin "89") (pinfunction "PD10_89") (pintype "bidirectional"))
      (node (ref "U102") (pin "2") (pinfunction "MISO/IO1_2") (pintype "output"))
    )
    (net (code "114") (name "QSPI_D2") (class "Default")
      (node (ref "U101") (pin "90") (pinfunction "PD11_90") (pintype "bidirectional"))
      (node (ref "U102") (pin "3") (pinfunction "~{WP}/IO2_3") (pintype "input"))
    )
    (net (code "115") (name "QSPI_D3") (class "Default")
      (node (ref "U101") (pin "91") (pinfunction "PD12_91") (pintype "bidirectional"))
      (node (ref "U102") (pin "7") (pinfunction "~{HOLD}/IO3_7") (pintype "input"))
    )
    (net (code "116") (name "SDIO-CD") (class "Default")
      (node (ref "J101") (pin "9") (pinfunction "CD_9") (pintype "bidirectional"))
      (node (ref "R106") (pin "P$1") (pinfunction "P$1_P$1") (pintype "bidirectional"))
      (node (ref "U101") (pin "86") (pinfunction "PF8_86") (pintype "bidirectional"))
    )
    (net (code "117") (name "SDIO-CLK") (class "Default")
      (node (ref "J101") (pin "5") (pinfunction "5_5") (pintype "bidirectional"))
      (node (ref "U101") (pin "97") (pinfunction "PE13_97") (pintype "bidirectional"))
    )
    (net (code "118") (name "SDIO-CMD") (class "Default")
      (node (ref "J101") (pin "3") (pinfunction "3_3") (pintype "bidirectional"))
      (node (ref "U101") (pin "96") (pinfunction "PE12_96") (pintype "bidirectional"))
    )
    (net (code "119") (name "SDIO-DAT0") (class "Default")
      (node (ref "J101") (pin "7") (pinfunction "7_7") (pintype "bidirectional"))
      (node (ref "U101") (pin "95") (pinfunction "PE11_95") (pintype "bidirectional"))
    )
    (net (code "120") (name "SDIO-DAT1") (class "Default")
      (node (ref "J101") (pin "8") (pinfunction "8_8") (pintype "bidirectional"))
      (node (ref "U101") (pin "94") (pinfunction "PE10_94") (pintype "bidirectional"))
    )
    (net (code "121") (name "SDIO-DAT2") (class "Default")
      (node (ref "J101") (pin "1") (pinfunction "1_1") (pintype "bidirectional"))
      (node (ref "U101") (pin "93") (pinfunction "PE9_93") (pintype "bidirectional"))
    )
    (net (code "122") (name "SDIO-DAT3") (class "Default")
      (node (ref "J101") (pin "2") (pinfunction "2_2") (pintype "bidirectional"))
      (node (ref "U101") (pin "92") (pinfunction "PE8_92") (pintype "bidirectional"))
    )
    (net (code "123") (name "SWCLK") (class "Default")
      (node (ref "J102") (pin "3") (pinfunction "S_3") (pintype "passive"))
      (node (ref "U101") (pin "76") (pinfunction "PF0_76") (pintype "bidirectional"))
    )
    (net (code "124") (name "SWDIO") (class "Default")
      (node (ref "J102") (pin "4") (pinfunction "S_4") (pintype "passive"))
      (node (ref "U101") (pin "77") (pinfunction "PF1_77") (pintype "bidirectional"))
    )
    (net (code "125") (name "SWO") (class "Default")
      (node (ref "J102") (pin "5") (pinfunction "S_5") (pintype "passive"))
      (node (ref "U101") (pin "78") (pinfunction "PF2_78") (pintype "bidirectional"))
    )
    (net (code "126") (name "TFT-DC") (class "Default")
      (node (ref "U101") (pin "26") (pinfunction "PA7_26") (pintype "bidirectional"))
      (node (ref "U204") (pin "37") (pinfunction "D/~{C}_37") (pintype "bidirectional"))
    )
    (net (code "127") (name "TIM0-CC0-BUZZ") (class "Default")
      (node (ref "R212") (pin "P$1") (pinfunction "P$1_P$1") (pintype "bidirectional"))
      (node (ref "U101") (pin "27") (pinfunction "PA8_27") (pintype "bidirectional"))
    )
    (net (code "128") (name "TIM1-CC0-TFT-BL") (class "Default")
      (node (ref "R203") (pin "P$1") (pinfunction "P$1_P$1") (pintype "bidirectional"))
      (node (ref "U101") (pin "9") (pinfunction "PB0_9") (pintype "bidirectional"))
    )
    (net (code "129") (name "TIM2-CC2FAN0-SNSE") (class "Default")
      (node (ref "R317") (pin "P$2") (pinfunction "P$2_P$2") (pintype "bidirectional"))
      (node (ref "R320") (pin "P$1") (pinfunction "P$1_P$1") (pintype "bidirectional"))
      (node (ref "U101") (pin "70") (pinfunction "PC10_70") (pintype "bidirectional"))
    )
    (net (code "130") (name "TIM3-CC0-FAN1-SNSE") (class "Default")
      (node (ref "R322") (pin "P$2") (pinfunction "P$2_P$2") (pintype "bidirectional"))
      (node (ref "R327") (pin "P$1") (pinfunction "P$1_P$1") (pintype "bidirectional"))
      (node (ref "U101") (pin "7") (pinfunction "PA6_7") (pintype "bidirectional"))
    )
    (net (code "131") (name "TIM5-CC0-FAN0-GND") (class "Default")
      (node (ref "R319") (pin "P$1") (pinfunction "P$1_P$1") (pintype "bidirectional"))
      (node (ref "U101") (pin "68") (pinfunction "PC8_68") (pintype "bidirectional"))
    )
    (net (code "132") (name "TIM5-CC1-FAN0-CTRL") (class "Default")
      (node (ref "R318") (pin "P$1") (pinfunction "P$1_P$1") (pintype "bidirectional"))
      (node (ref "U101") (pin "69") (pinfunction "PC9_69") (pintype "bidirectional"))
    )
    (net (code "133") (name "TIM6-CC0-FAN1-GND") (class "Default")
      (node (ref "R325") (pin "P$1") (pinfunction "P$1_P$1") (pintype "bidirectional"))
      (node (ref "U101") (pin "46") (pinfunction "PD1_46") (pintype "bidirectional"))
    )
    (net (code "134") (name "TIM6-CC1-FAN1-CTRL") (class "Default")
      (node (ref "R324") (pin "P$1") (pinfunction "P$1_P$1") (pintype "bidirectional"))
      (node (ref "U101") (pin "47") (pinfunction "PD2_47") (pintype "bidirectional"))
    )
    (net (code "135") (name "U0RX-USB-TX") (class "Default")
      (node (ref "U101") (pin "5") (pinfunction "PA4_5") (pintype "bidirectional"))
      (node (ref "U205") (pin "21") (pinfunction "TXD_21") (pintype "bidirectional"))
    )
    (net (code "136") (name "U0TX-USB-RX") (class "Default")
      (node (ref "U101") (pin "4") (pinfunction "PA3_4") (pintype "bidirectional"))
      (node (ref "U205") (pin "20") (pinfunction "RXD_20") (pintype "bidirectional"))
    )
    (net (code "137") (name "U1RX-BLE-TX") (class "Default")
      (node (ref "M201") (pin "2") (pinfunction "TX_2") (pintype "bidirectional"))
      (node (ref "U101") (pin "63") (pinfunction "PE3_63") (pintype "bidirectional"))
    )
    (net (code "138") (name "U1TX-BLE-RX") (class "Default")
      (node (ref "M201") (pin "4") (pinfunction "RX_4") (pintype "bidirectional"))
      (node (ref "U101") (pin "62") (pinfunction "PE2_62") (pintype "bidirectional"))
    )
    (net (code "139") (name "UART_VBUS") (class "Default")
      (node (ref "R207") (pin "P$1") (pinfunction "P$1_P$1") (pintype "bidirectional"))
      (node (ref "R208") (pin "P$2") (pinfunction "P$2_P$2") (pintype "bidirectional"))
      (node (ref "U205") (pin "8") (pinfunction "VBUS_8") (pintype "bidirectional"))
    )
    (net (code "140") (name "US0-LED-MOSI") (class "Default")
      (node (ref "U101") (pin "67") (pinfunction "PE7_67") (pintype "bidirectional"))
      (node (ref "U201") (pin "2") (pinfunction "A_2") (pintype "input"))
    )
    (net (code "141") (name "US0-LED-SCK") (class "Default")
      (node (ref "U101") (pin "65") (pinfunction "PE5_65") (pintype "bidirectional"))
      (node (ref "U201") (pin "1") (pinfunction "B_1") (pintype "input"))
      (node (ref "U202") (pin "10") (pinfunction "B_10") (pintype "bidirectional"))
    )
    (net (code "142") (name "US1-CLK-TFT") (class "Default")
      (node (ref "U101") (pin "21") (pinfunction "PC3_21") (pintype "bidirectional"))
      (node (ref "U204") (pin "36") (pinfunction "~{WR}/SCL_36") (pintype "bidirectional"))
    )
    (net (code "143") (name "US1-CS-TFT") (class "Default")
      (node (ref "R206") (pin "P$1") (pinfunction "P$1_P$1") (pintype "bidirectional"))
      (node (ref "U101") (pin "18") (pinfunction "PC0_18") (pintype "bidirectional"))
      (node (ref "U204") (pin "38") (pinfunction "~{CS}_38") (pintype "bidirectional"))
    )
    (net (code "144") (name "US1-MISO-TFT") (class "Default")
      (node (ref "U101") (pin "20") (pinfunction "PC2_20") (pintype "bidirectional"))
      (node (ref "U204") (pin "33") (pinfunction "SDO_33") (pintype "bidirectional"))
    )
    (net (code "145") (name "US1-MOSI-TFT") (class "Default")
      (node (ref "U101") (pin "19") (pinfunction "PC1_19") (pintype "bidirectional"))
      (node (ref "U204") (pin "34") (pinfunction "SDA_34") (pintype "bidirectional"))
    )
    (net (code "146") (name "USB-D+") (class "Default")
      (node (ref "JP202") (pin "1") (pinfunction "1_1") (pintype "passive"))
      (node (ref "U101") (pin "75") (pinfunction "PF11_75") (pintype "bidirectional"))
    )
    (net (code "147") (name "USB-D-") (class "Default")
      (node (ref "JP201") (pin "1") (pinfunction "1_1") (pintype "passive"))
      (node (ref "U101") (pin "74") (pinfunction "PF10_74") (pintype "bidirectional"))
    )
    (net (code "148") (name "USB-ID") (class "Default")
      (node (ref "J201") (pin "ID") (pinfunction "ID_ID") (pintype "bidirectional"))
      (node (ref "U101") (pin "80") (pinfunction "PF12_80") (pintype "bidirectional"))
    )
    (net (code "149") (name "USB-RST") (class "Default")
      (node (ref "U101") (pin "3") (pinfunction "PA2_3") (pintype "bidirectional"))
      (node (ref "U205") (pin "9") (pinfunction "RSTB_9") (pintype "bidirectional"))
    )
    (net (code "150") (name "USB-SUS") (class "Default")
      (node (ref "U101") (pin "2") (pinfunction "PA1_2") (pintype "bidirectional"))
      (node (ref "U205") (pin "17") (pinfunction "SUSPEND_17") (pintype "bidirectional"))
    )
    (net (code "151") (name "USB-UART-D+") (class "Default")
      (node (ref "JP202") (pin "3") (pinfunction "3_3") (pintype "passive"))
      (node (ref "U205") (pin "3") (pinfunction "D+_3") (pintype "bidirectional"))
    )
    (net (code "152") (name "USB-UART-D-") (class "Default")
      (node (ref "JP201") (pin "3") (pinfunction "3_3") (pintype "passive"))
      (node (ref "U205") (pin "4") (pinfunction "D-_4") (pintype "bidirectional"))
    )
    (net (code "153") (name "V-USB") (class "Default")
      (node (ref "D206") (pin "4") (pinfunction "4_4") (pintype "bidirectional"))
      (node (ref "J201") (pin "VBUS") (pinfunction "VBUS_VBUS") (pintype "bidirectional"))
      (node (ref "R207") (pin "P$2") (pinfunction "P$2_P$2") (pintype "bidirectional"))
      (node (ref "TP202") (pin "1") (pinfunction "S_1") (pintype "passive"))
    )
    (net (code "154") (name "WTIM1-CC1-ZERO-CROSS") (class "Default")
      (node (ref "R316") (pin "P$1") (pinfunction "P$1_P$1") (pintype "bidirectional"))
      (node (ref "TP302") (pin "1") (pinfunction "S_1") (pintype "passive"))
      (node (ref "U101") (pin "64") (pinfunction "PE4_64") (pintype "bidirectional"))
      (node (ref "U303") (pin "P$5") (pinfunction "C_P$5") (pintype "bidirectional"))
    )
    (net (code "155") (name "WTIM2-CC0-SERVO0-SIG") (class "Default")
      (node (ref "R301") (pin "P$1") (pinfunction "P$1_P$1") (pintype "bidirectional"))
      (node (ref "U101") (pin "48") (pinfunction "PD3_48") (pintype "bidirectional"))
    )
    (net (code "156") (name "WTIM2-CC1-SERVO1-SIG") (class "Default")
      (node (ref "R303") (pin "P$1") (pinfunction "P$1_P$1") (pintype "bidirectional"))
      (node (ref "U101") (pin "49") (pinfunction "PD4_49") (pintype "bidirectional"))
    )
    (net (code "157") (name "unconnected-(D205-DO-Pad4)") (class "Default")
      (node (ref "D205") (pin "4") (pinfunction "DO_4") (pintype "bidirectional"))
    )
    (net (code "158") (name "unconnected-(M201-CTS-Pad3)") (class "Default")
      (node (ref "M201") (pin "3") (pinfunction "CTS_3") (pintype "bidirectional"))
    )
    (net (code "159") (name "unconnected-(M201-PIO2-Pad14)") (class "Default")
      (node (ref "M201") (pin "14") (pinfunction "PIO2_14") (pintype "bidirectional"))
    )
    (net (code "160") (name "unconnected-(M201-PIO3-Pad13)") (class "Default")
      (node (ref "M201") (pin "13") (pinfunction "PIO3_13") (pintype "bidirectional"))
    )
    (net (code "161") (name "unconnected-(M201-RTS-Pad1)") (class "Default")
      (node (ref "M201") (pin "1") (pinfunction "RTS_1") (pintype "bidirectional"))
    )
    (net (code "162") (name "unconnected-(U202A-~{Q}-Pad4)") (class "Default")
      (node (ref "U202") (pin "4") (pinfunction "~{Q}_4") (pintype "bidirectional"))
    )
    (net (code "163") (name "unconnected-(U202B-~{Q}-Pad12)") (class "Default")
      (node (ref "U202") (pin "12") (pinfunction "~{Q}_12") (pintype "bidirectional"))
    )
    (net (code "164") (name "unconnected-(U205-CTS-Pad18)") (class "Default")
      (node (ref "U205") (pin "18") (pinfunction "CTS_18") (pintype "bidirectional"))
    )
    (net (code "165") (name "unconnected-(U205-DCD-Pad24)") (class "Default")
      (node (ref "U205") (pin "24") (pinfunction "DCD_24") (pintype "bidirectional"))
    )
    (net (code "166") (name "unconnected-(U205-DSR-Pad22)") (class "Default")
      (node (ref "U205") (pin "22") (pinfunction "DSR_22") (pintype "bidirectional"))
    )
    (net (code "167") (name "unconnected-(U205-DTR-Pad23)") (class "Default")
      (node (ref "U205") (pin "23") (pinfunction "DTR_23") (pintype "bidirectional"))
    )
    (net (code "168") (name "unconnected-(U205-GPIO2-RS485-Pad12)") (class "Default")
      (node (ref "U205") (pin "12") (pinfunction "GPIO2-RS485_12") (pintype "bidirectional"))
    )
    (net (code "169") (name "unconnected-(U205-GPIO3-WKUP-Pad11)") (class "Default")
      (node (ref "U205") (pin "11") (pinfunction "GPIO3-WKUP_11") (pintype "bidirectional"))
    )
    (net (code "170") (name "unconnected-(U205-RI{slash}CLK-Pad1)") (class "Default")
      (node (ref "U205") (pin "1") (pinfunction "RI/CLK_1") (pintype "bidirectional"))
    )
    (net (code "171") (name "unconnected-(U205-RTS-Pad19)") (class "Default")
      (node (ref "U205") (pin "19") (pinfunction "RTS_19") (pintype "bidirectional"))
    )
    (net (code "172") (name "unconnected-(U205-SUSPENDB-Pad15)") (class "Default")
      (node (ref "U205") (pin "15") (pinfunction "SUSPENDB_15") (pintype "bidirectional"))
    )
    (net (code "173") (name "unconnected-(U301-ALERT4-Pad15)") (class "Default")
      (node (ref "U301") (pin "15") (pinfunction "ALERT4_15") (pintype "bidirectional"))
    )
    (net (code "174") (name "unconnected-(U301-ALRT2-Pad12)") (class "Default")
      (node (ref "U301") (pin "12") (pinfunction "ALRT2_12") (pintype "bidirectional"))
    )
    (net (code "175") (name "unconnected-(U301-ALRT3-Pad14)") (class "Default")
      (node (ref "U301") (pin "14") (pinfunction "ALRT3_14") (pintype "bidirectional"))
    )
    (net (code "176") (name "unconnected-(U302-ALERT4-Pad15)") (class "Default")
      (node (ref "U302") (pin "15") (pinfunction "ALERT4_15") (pintype "bidirectional"))
    )
    (net (code "177") (name "unconnected-(U302-ALRT2-Pad12)") (class "Default")
      (node (ref "U302") (pin "12") (pinfunction "ALRT2_12") (pintype "bidirectional"))
    )
    (net (code "178") (name "unconnected-(U302-ALRT3-Pad14)") (class "Default")
      (node (ref "U302") (pin "14") (pinfunction "ALRT3_14") (pintype "bidirectional"))
    )
    (net (code "179") (name "unconnected-(U303-B-PadP$6)") (class "Default")
      (node (ref "U303") (pin "P$6") (pinfunction "B_P$6") (pintype "bidirectional"))
    )
    (net (code "180") (name "~{LED-CS}") (class "Default")
      (node (ref "U101") (pin "66") (pinfunction "PE6_66") (pintype "bidirectional"))
      (node (ref "U202") (pin "1") (pinfunction "~{A}_1") (pintype "bidirectional"))
      (node (ref "U202") (pin "9") (pinfunction "~{A}_9") (pintype "bidirectional"))
    )
    (net (code "181") (name "~{RESET}") (class "Default")
      (node (ref "J102") (pin "2") (pinfunction "S_2") (pintype "passive"))
      (node (ref "SW101") (pin "1") (pinfunction "1_1") (pintype "passive"))
      (node (ref "SW101") (pin "2") (pinfunction "2_2") (pintype "passive"))
      (node (ref "U101") (pin "36") (pinfunction "~{RESET}_36") (pintype "bidirectional"))
    )
    (net (code "182") (name "~{TFT_RESET}") (class "Default")
      (node (ref "U101") (pin "14") (pinfunction "PB5_14") (pintype "bidirectional"))
      (node (ref "U204") (pin "10") (pinfunction "~{RESET}_10") (pintype "bidirectional"))
    )
    (net (code "183") (name "~{TTFT-IRQ}") (class "Default")
      (node (ref "U101") (pin "12") (pinfunction "PB3_12") (pintype "bidirectional"))
      (node (ref "U204") (pin "46") (pinfunction "X-/~{IRQ}_46") (pintype "bidirectional"))
    )
    (net (code "184") (name "~{TTFT-RST}") (class "Default")
      (node (ref "U101") (pin "15") (pinfunction "PB6_15") (pintype "bidirectional"))
      (node (ref "U204") (pin "47") (pinfunction "Y-/~{RST}_47") (pintype "bidirectional"))
    )
  )
)
